# PocketCHIP-v1_0.net
KiCad netlist of a schematic drawn in EAGLE
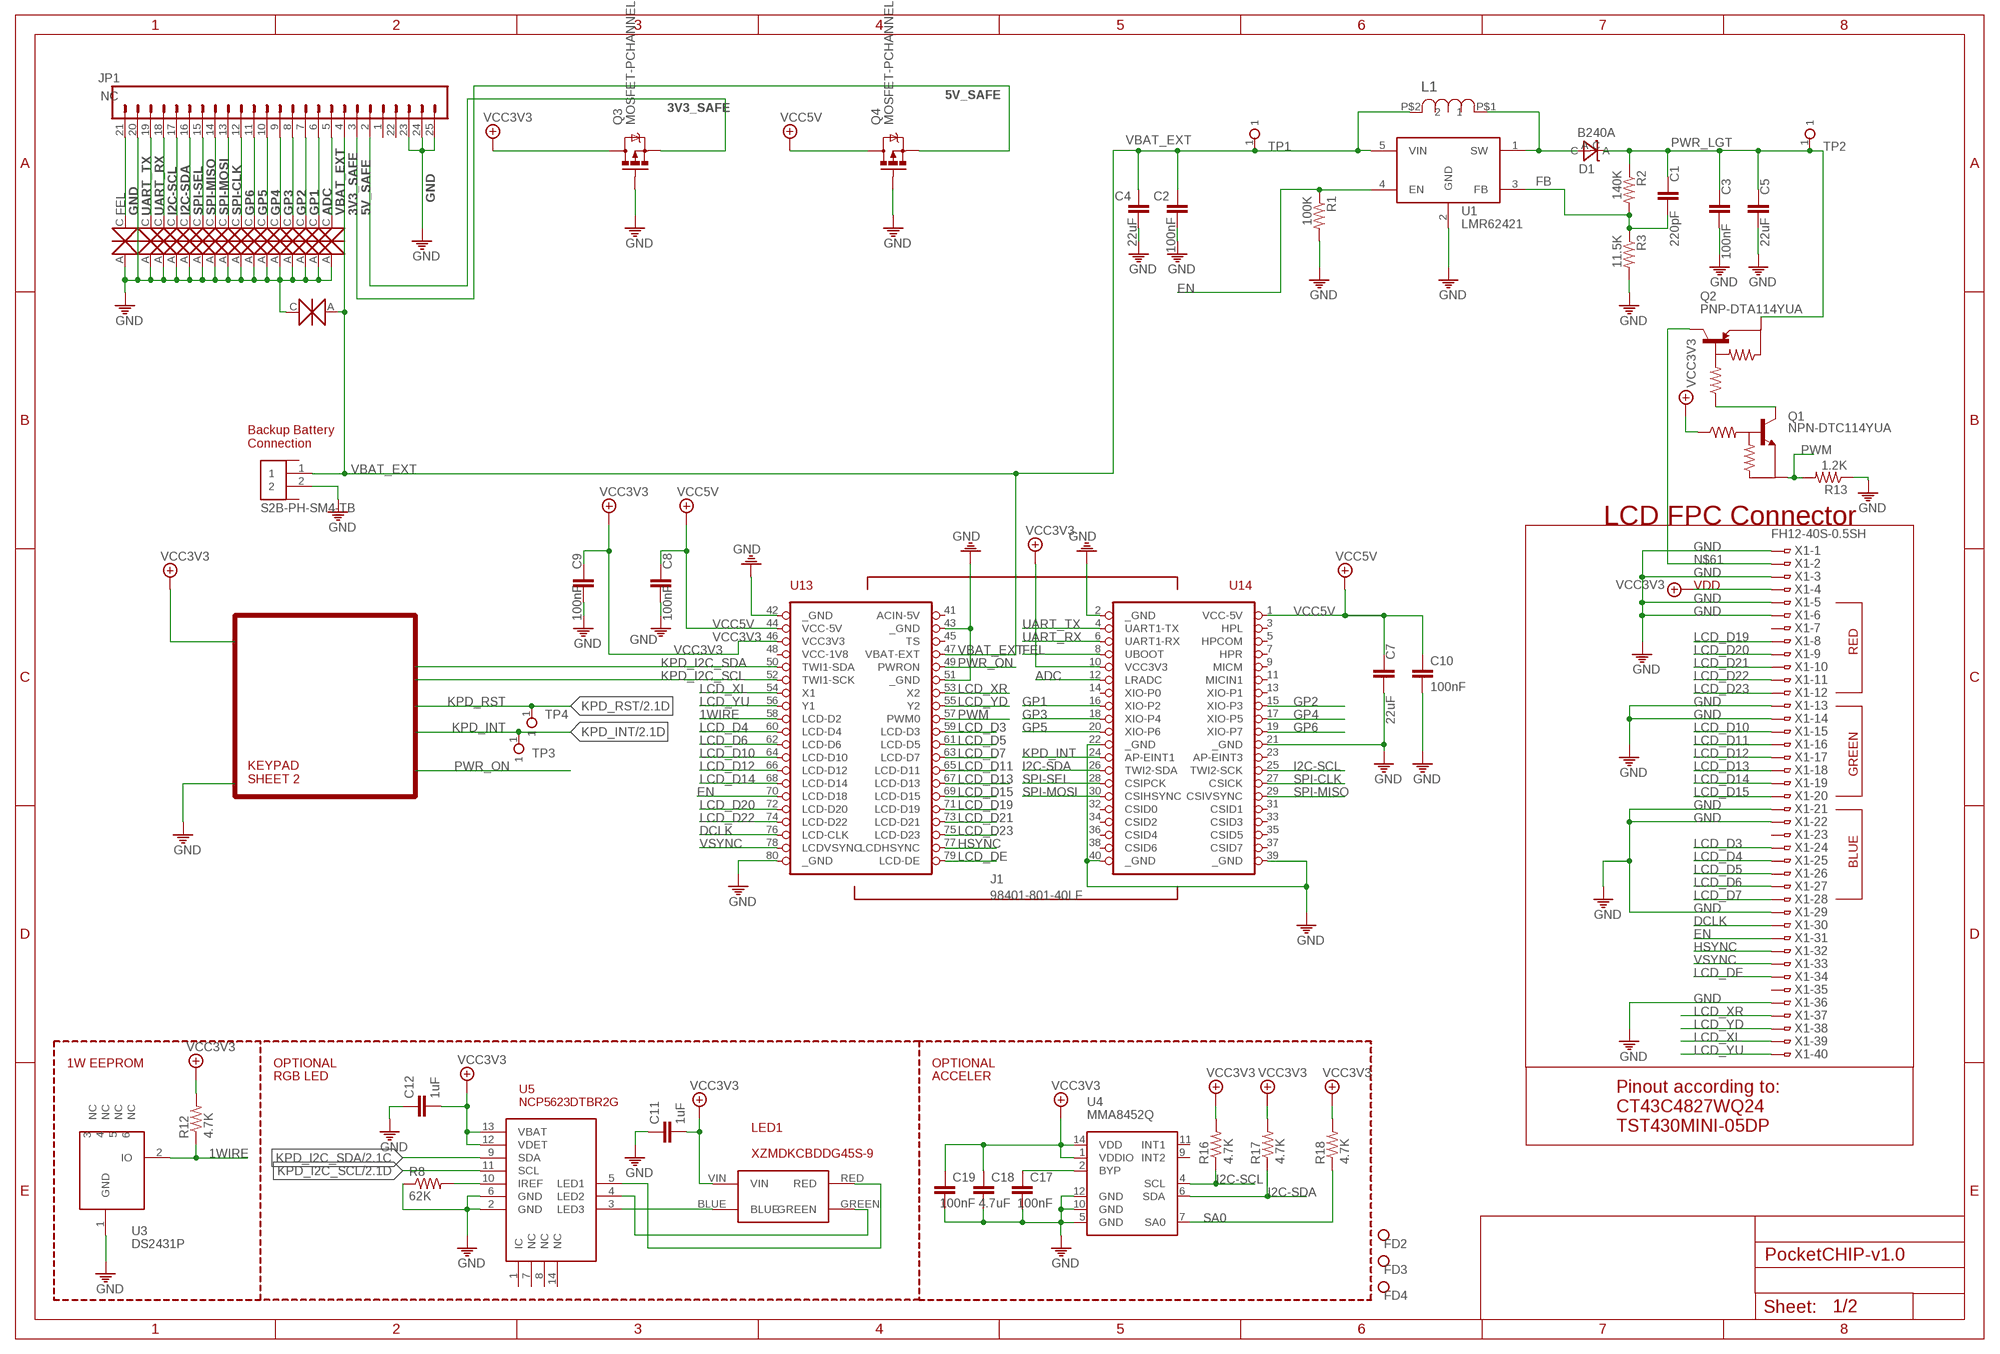
[diagram p0: schematic, sheet 1]
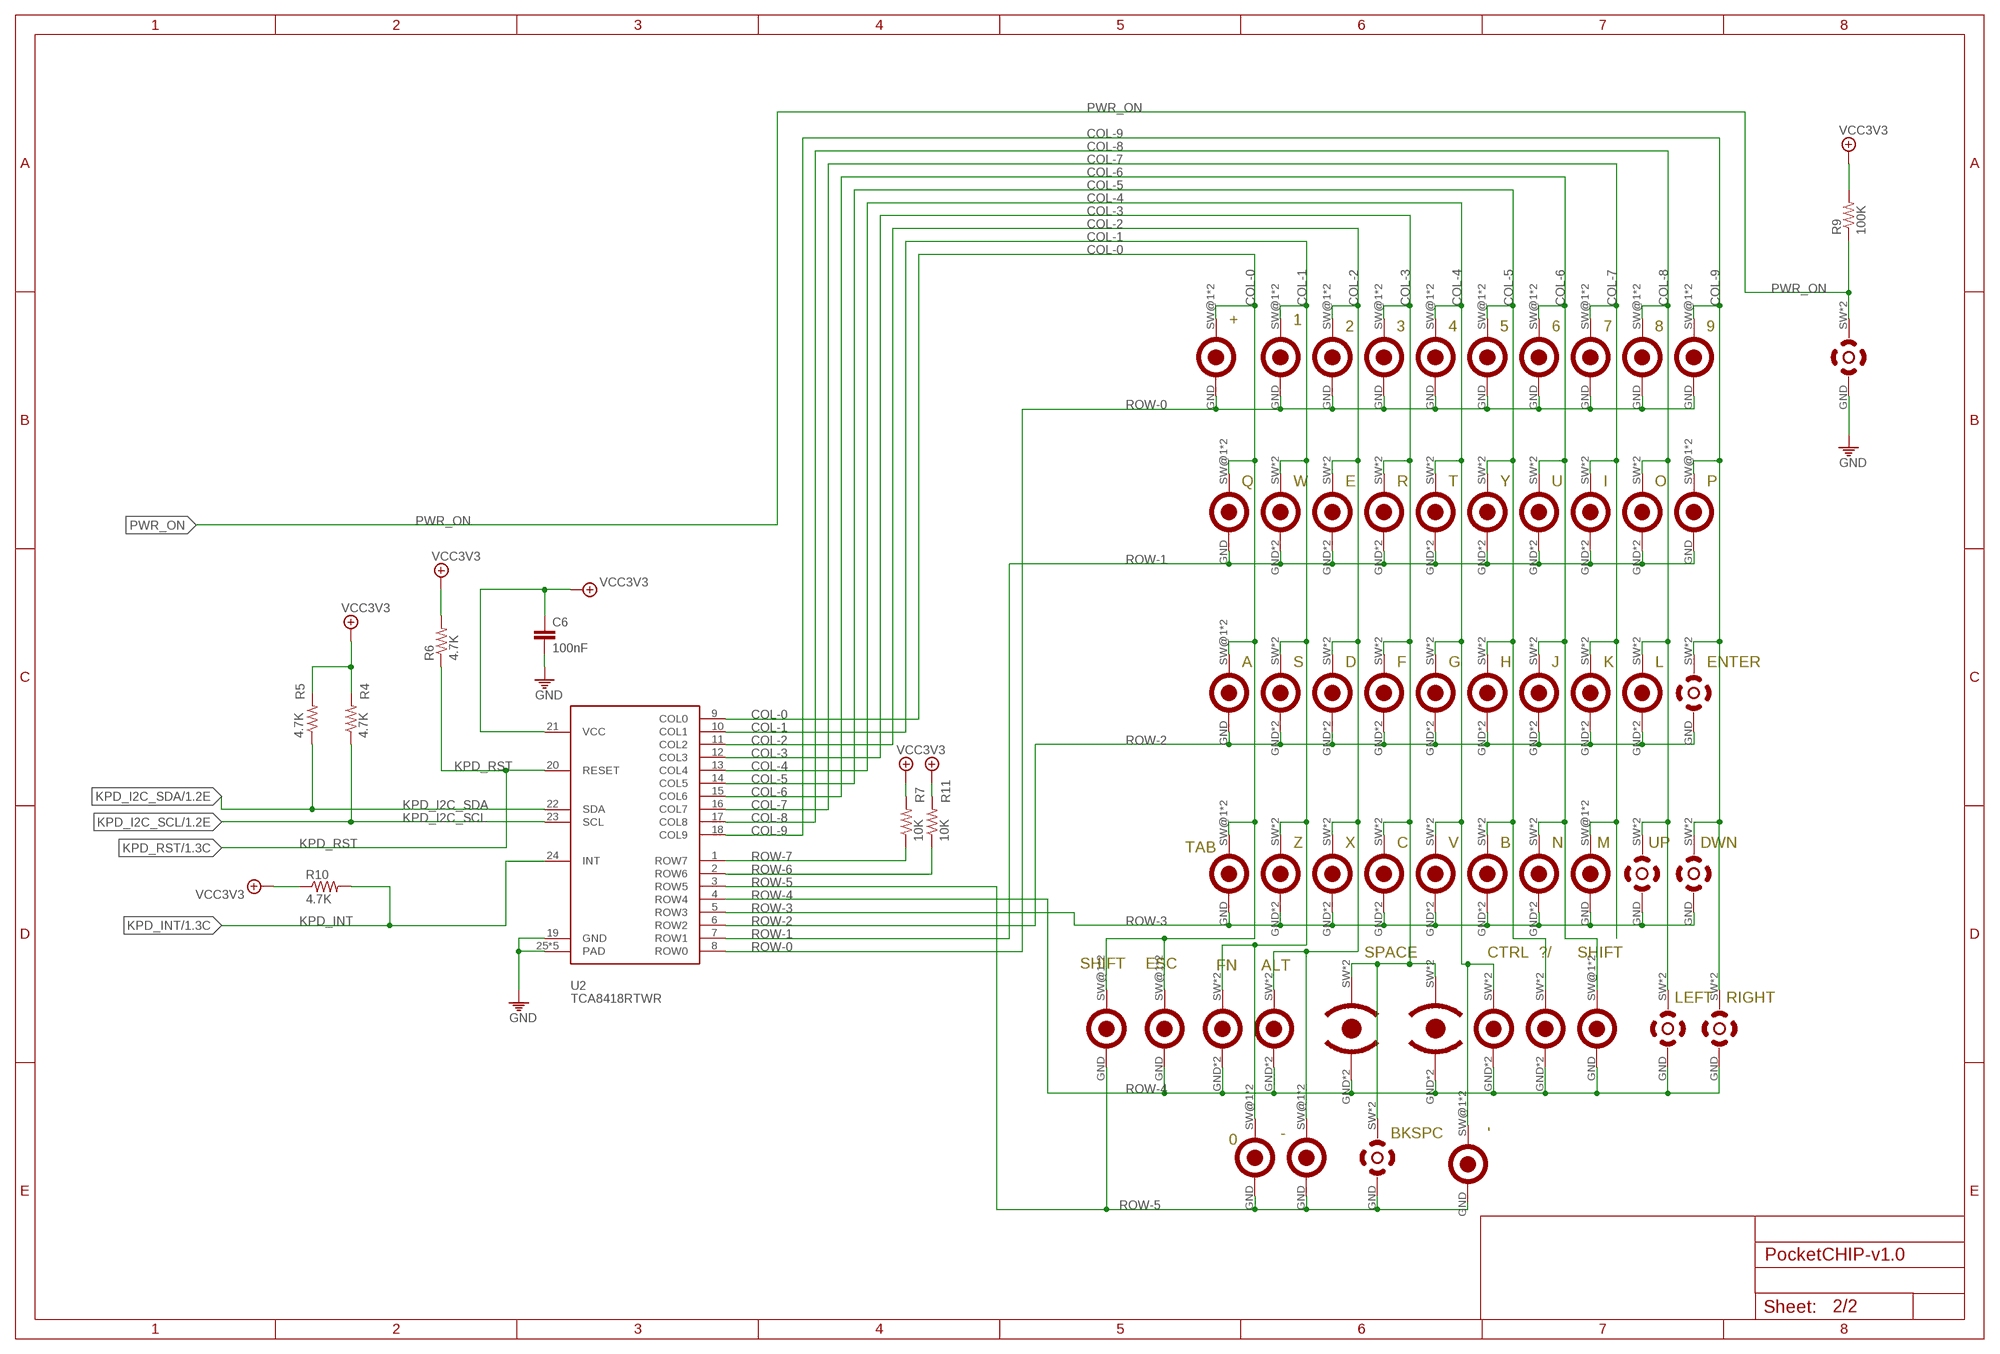
[diagram p1: schematic, sheet 2]

(export (version "E")
  (design (tool "Eeschema 10.0.6"))
  (components
    (comp (ref "C1")
      (value "220pF")
      (footprint "eagle-import:C0402")
      (fields (field (name "MFG") "DIGIIKEY") (field (name "VENDOR_PART_NUMBER") "C0402C221J5GACTU"))
      (libsource (lib "eagle-import") (part "C0402_220PF_50V_5%"))
    )
    (comp (ref "C2")
      (value "100nF")
      (footprint "eagle-import:C0402")
      (fields (field (name "MFG") "DIGIIKEY") (field (name "VENDOR_PART_NUMBER") "C1005X5R1E104K050BC"))
      (libsource (lib "eagle-import") (part "C0402_100NF_50V_10%"))
    )
    (comp (ref "C3")
      (value "100nF")
      (footprint "eagle-import:C0402")
      (fields (field (name "MFG") "DIGIIKEY") (field (name "VENDOR_PART_NUMBER") "C1005X5R1E104K050BC"))
      (libsource (lib "eagle-import") (part "C0402_100NF_50V_10%"))
    )
    (comp (ref "C4")
      (value "22uF")
      (footprint "eagle-import:C1206")
      (fields (field (name "MFG") "DIGIKEY") (field (name "VENDOR_PART_NUMBER") "C3216X5R1V226M160AC"))
      (libsource (lib "eagle-import") (part "C1206_22UF_50V_10%"))
    )
    (comp (ref "C5")
      (value "22uF")
      (footprint "eagle-import:C1206")
      (fields (field (name "MFG") "DIGIKEY") (field (name "VENDOR_PART_NUMBER") "C3216X5R1V226M160AC"))
      (libsource (lib "eagle-import") (part "C1206_22UF_50V_10%"))
    )
    (comp (ref "C7")
      (value "22uF")
      (footprint "eagle-import:C1206")
      (fields (field (name "MFG") "DIGIKEY") (field (name "VENDOR_PART_NUMBER") "C3216X5R1V226M160AC"))
      (libsource (lib "eagle-import") (part "C1206_22UF_50V_10%"))
    )
    (comp (ref "C8")
      (value "100nF")
      (footprint "eagle-import:C0402")
      (fields (field (name "MFG") "DIGIIKEY") (field (name "VENDOR_PART_NUMBER") "C1005X5R1E104K050BC"))
      (libsource (lib "eagle-import") (part "C0402_100NF_50V_10%"))
    )
    (comp (ref "C9")
      (value "100nF")
      (footprint "eagle-import:C0402")
      (fields (field (name "MFG") "DIGIIKEY") (field (name "VENDOR_PART_NUMBER") "C1005X5R1E104K050BC"))
      (libsource (lib "eagle-import") (part "C0402_100NF_50V_10%"))
    )
    (comp (ref "C10")
      (value "100nF")
      (footprint "eagle-import:C0402")
      (fields (field (name "MFG") "DIGIIKEY") (field (name "VENDOR_PART_NUMBER") "C1005X5R1E104K050BC"))
      (libsource (lib "eagle-import") (part "C0402_100NF_50V_10%"))
    )
    (comp (ref "C11")
      (value "1uF")
      (footprint "eagle-import:C0402")
      (fields (field (name "MFG") "DIGIIKEY") (field (name "VENDOR_PART_NUMBER") "C1005X5R1E104K050BC"))
      (libsource (lib "eagle-import") (part "C0402_1UF_50V_10%"))
    )
    (comp (ref "C12")
      (value "1uF")
      (footprint "eagle-import:C0402")
      (fields (field (name "MFG") "DIGIIKEY") (field (name "VENDOR_PART_NUMBER") "C1005X5R1E104K050BC"))
      (libsource (lib "eagle-import") (part "C0402_1UF_50V_10%"))
    )
    (comp (ref "C17")
      (value "100nF")
      (footprint "eagle-import:C0402")
      (fields (field (name "MFG") "DIGIIKEY") (field (name "VENDOR_PART_NUMBER") "C1005X5R1E104K050BC"))
      (libsource (lib "eagle-import") (part "PocketCHIP-Components-v0.71_C0402_100NF_50V_10%"))
    )
    (comp (ref "C18")
      (value "4.7uF")
      (footprint "eagle-import:C0402")
      (fields (field (name "MFG") "DIGIIKEY") (field (name "VENDOR_PART_NUMBER") "C1005X5R1E104K050BC"))
      (libsource (lib "eagle-import") (part "PocketCHIP-Components-v0.71_C0402_100NF_50V_10%"))
    )
    (comp (ref "C19")
      (value "100nF")
      (footprint "eagle-import:C0402")
      (fields (field (name "MFG") "DIGIIKEY") (field (name "VENDOR_PART_NUMBER") "C1005X5R1E104K050BC"))
      (libsource (lib "eagle-import") (part "PocketCHIP-Components-v0.71_C0402_100NF_50V_10%"))
    )
    (comp (ref "D1")
      (value "B240A")
      (footprint "eagle-import:DO-214AC")
      (fields (field (name "MFG") "DIGIKEY") (field (name "VENDOR_PART_NUMBER") "B240A-13-F"))
      (libsource (lib "eagle-import") (part "DIODE_SCHTKY_B240"))
    )
    (comp (ref "ESD1")
      (value "ESD5Z2.5T1G")
      (footprint "eagle-import:SOD523")
      (libsource (lib "eagle-import") (part "ESD5Z2.5T1G"))
    )
    (comp (ref "ESD2")
      (value "ESD5Z2.5T1G")
      (footprint "eagle-import:SOD523")
      (libsource (lib "eagle-import") (part "ESD5Z2.5T1G"))
    )
    (comp (ref "ESD3")
      (value "ESD5Z2.5T1G")
      (footprint "eagle-import:SOD523")
      (libsource (lib "eagle-import") (part "ESD5Z2.5T1G"))
    )
    (comp (ref "ESD4")
      (value "ESD5Z2.5T1G")
      (footprint "eagle-import:SOD523")
      (libsource (lib "eagle-import") (part "ESD5Z2.5T1G"))
    )
    (comp (ref "ESD5")
      (value "ESD5Z2.5T1G")
      (footprint "eagle-import:SOD523")
      (libsource (lib "eagle-import") (part "ESD5Z2.5T1G"))
    )
    (comp (ref "ESD6")
      (value "ESD5Z2.5T1G")
      (footprint "eagle-import:SOD523")
      (libsource (lib "eagle-import") (part "ESD5Z2.5T1G"))
    )
    (comp (ref "ESD7")
      (value "ESD5Z2.5T1G")
      (footprint "eagle-import:SOD523")
      (libsource (lib "eagle-import") (part "ESD5Z2.5T1G"))
    )
    (comp (ref "ESD8")
      (value "ESD5Z2.5T1G")
      (footprint "eagle-import:SOD523")
      (libsource (lib "eagle-import") (part "ESD5Z2.5T1G"))
    )
    (comp (ref "ESD9")
      (value "ESD5Z2.5T1G")
      (footprint "eagle-import:SOD523")
      (libsource (lib "eagle-import") (part "ESD5Z2.5T1G"))
    )
    (comp (ref "ESD10")
      (value "ESD5Z2.5T1G")
      (footprint "eagle-import:SOD523")
      (libsource (lib "eagle-import") (part "ESD5Z2.5T1G"))
    )
    (comp (ref "ESD11")
      (value "ESD5Z2.5T1G")
      (footprint "eagle-import:SOD523")
      (libsource (lib "eagle-import") (part "ESD5Z2.5T1G"))
    )
    (comp (ref "ESD12")
      (value "ESD5Z2.5T1G")
      (footprint "eagle-import:SOD523")
      (libsource (lib "eagle-import") (part "ESD5Z2.5T1G"))
    )
    (comp (ref "ESD13")
      (value "ESD5Z2.5T1G")
      (footprint "eagle-import:SOD523")
      (libsource (lib "eagle-import") (part "ESD5Z2.5T1G"))
    )
    (comp (ref "ESD14")
      (value "ESD5Z2.5T1G")
      (footprint "eagle-import:SOD523")
      (libsource (lib "eagle-import") (part "ESD5Z2.5T1G"))
    )
    (comp (ref "ESD15")
      (value "ESD5Z2.5T1G")
      (footprint "eagle-import:SOD523")
      (libsource (lib "eagle-import") (part "ESD5Z2.5T1G"))
    )
    (comp (ref "ESD16")
      (value "ESD5Z2.5T1G")
      (footprint "eagle-import:SOD523")
      (libsource (lib "eagle-import") (part "ESD5Z2.5T1G"))
    )
    (comp (ref "ESD17")
      (value "ESD5Z2.5T1G")
      (footprint "eagle-import:SOD523")
      (libsource (lib "eagle-import") (part "ESD5Z2.5T1G"))
    )
    (comp (ref "FD2")
      (value "FIDUCIAL")
      (footprint "eagle-import:FIDUCIAL_1MM")
      (fields (field (name "PART_NUMBER") "RB00000042"))
      (libsource (lib "eagle-import") (part "FIDUCIAL"))
    )
    (comp (ref "FD3")
      (value "FIDUCIAL")
      (footprint "eagle-import:FIDUCIAL_1MM")
      (fields (field (name "PART_NUMBER") "RB00000042"))
      (libsource (lib "eagle-import") (part "FIDUCIAL"))
    )
    (comp (ref "FD4")
      (value "FIDUCIAL")
      (footprint "eagle-import:FIDUCIAL_1MM")
      (fields (field (name "PART_NUMBER") "RB00000042"))
      (libsource (lib "eagle-import") (part "FIDUCIAL"))
    )
    (comp (ref "J1")
      (value "98401-801-40LF")
      (footprint "eagle-import:98401-801-40LF")
      (libsource (lib "eagle-import") (part "98401-801-40LF"))
    )
    (comp (ref "J3")
      (value "S2B-PH-SM4-TB")
      (footprint "eagle-import:S2B-PH-SM4-TB")
      (fields (field (name "MFG") "DIGIKEY") (field (name "VENDOR_PART_NUMBER") "S2B-PH-SM4-TB(LF)(SN)"))
      (libsource (lib "eagle-import") (part "S2B-PH-SM4-TB"))
    )
    (comp (ref "JP1")
      (value "NC")
      (footprint "eagle-import:1X20_LOCK_LONGPADS")
      (libsource (lib "eagle-import") (part "M20LOCK_LONGPADS"))
    )
    (comp (ref "L1")
      (value "SRN6045-100M")
      (footprint "eagle-import:SRN6045")
      (fields (field (name "MFG") "DIGIKEY"))
      (libsource (lib "eagle-import") (part "SRN6045-100M"))
    )
    (comp (ref "LED1")
      (value "XZMDKCBDDG45S-9")
      (footprint "eagle-import:XZMDKCBDDG45S-9")
      (libsource (lib "eagle-import") (part "XZMDKCBDDG45S-9"))
    )
    (comp (ref "Q1")
      (value "NPN-DTC114YUA")
      (footprint "eagle-import:SOT323")
      (libsource (lib "eagle-import") (part "NPN-DTC114YUA"))
    )
    (comp (ref "Q2")
      (value "PNP-DTA114YUA")
      (footprint "eagle-import:SOT323")
      (libsource (lib "eagle-import") (part "PNP-DTA114YUA"))
    )
    (comp (ref "Q3")
      (value "MOSFET-PCHANNEL")
      (footprint "eagle-import:SOT23-3")
      (libsource (lib "eagle-import") (part "MOSFET-PCHANNEL"))
    )
    (comp (ref "Q4")
      (value "MOSFET-PCHANNEL")
      (footprint "eagle-import:SOT23-3")
      (libsource (lib "eagle-import") (part "MOSFET-PCHANNEL"))
    )
    (comp (ref "R1")
      (value "100K")
      (footprint "eagle-import:R0402")
      (fields (field (name "MFG") "DIGIKEY") (field (name "VENDOR_PART_NUMBER") "ERJ-2GEJ104X"))
      (libsource (lib "eagle-import") (part "R0402_100K_5%"))
    )
    (comp (ref "R2")
      (value "140K")
      (footprint "eagle-import:R0402")
      (fields (field (name "MFG") "DIGIKEY") (field (name "VENDOR_PART_NUMBER") "RC0402FR-07140KL"))
      (libsource (lib "eagle-import") (part "R0402_140K_1%"))
    )
    (comp (ref "R3")
      (value "11.5K")
      (footprint "eagle-import:R0402")
      (fields (field (name "MFG") "DIGIKEY") (field (name "VENDOR_PART_NUMBER") "RC0402FR-0711K5L"))
      (libsource (lib "eagle-import") (part "R0402_11K5_1%"))
    )
    (comp (ref "R8")
      (value "62K")
      (footprint "eagle-import:R0402")
      (fields (field (name "MFG") "DIGIKEY") (field (name "VENDOR_PART_NUMBER") "ERJ-2GEJ102X"))
      (libsource (lib "eagle-import") (part "R0402_62K_5%"))
    )
    (comp (ref "R12")
      (value "4.7K")
      (footprint "eagle-import:R0402")
      (fields (field (name "MFG") "DIGIKEY") (field (name "VENDOR_PART_NUMBER") "ERJ-2GEJ472X"))
      (libsource (lib "eagle-import") (part "R0402_4K7_5%"))
    )
    (comp (ref "R13")
      (value "1.2K")
      (footprint "eagle-import:R0402")
      (fields (field (name "MFG") "DIGIKEY") (field (name "VENDOR_PART_NUMBER") "ERJ-2GEJ102X"))
      (libsource (lib "eagle-import") (part "PocketCHIP-Components-v0.72_R0402_1K_5%"))
    )
    (comp (ref "R16")
      (value "4.7K")
      (footprint "eagle-import:R0402")
      (fields (field (name "MFG") "DIGIKEY") (field (name "VENDOR_PART_NUMBER") "ERJ-2GEJ472X"))
      (libsource (lib "eagle-import") (part "PocketCHIP-Components-v0.71_R0402_4K7_5%"))
    )
    (comp (ref "R17")
      (value "4.7K")
      (footprint "eagle-import:R0402")
      (fields (field (name "MFG") "DIGIKEY") (field (name "VENDOR_PART_NUMBER") "ERJ-2GEJ472X"))
      (libsource (lib "eagle-import") (part "PocketCHIP-Components-v0.71_R0402_4K7_5%"))
    )
    (comp (ref "R18")
      (value "4.7K")
      (footprint "eagle-import:R0402")
      (fields (field (name "MFG") "DIGIKEY") (field (name "VENDOR_PART_NUMBER") "ERJ-2GEJ472X"))
      (libsource (lib "eagle-import") (part "PocketCHIP-Components-v0.71_R0402_4K7_5%"))
    )
    (comp (ref "TP1")
      (value "N.C")
      (footprint "eagle-import:TP_19_5")
      (fields (field (name "PART_NUMBER") "RB00000140"))
      (libsource (lib "eagle-import") (part "PocketCHIP-Components-v0.71_TP_SMD_0_5MM"))
    )
    (comp (ref "TP2")
      (value "N.C")
      (footprint "eagle-import:TP_19_5")
      (fields (field (name "PART_NUMBER") "RB00000140"))
      (libsource (lib "eagle-import") (part "PocketCHIP-Components-v0.71_TP_SMD_0_5MM"))
    )
    (comp (ref "TP3")
      (value "N.C")
      (footprint "eagle-import:TP_19_5")
      (fields (field (name "PART_NUMBER") "RB00000140"))
      (libsource (lib "eagle-import") (part "TP_SMD_0_5MM"))
    )
    (comp (ref "TP4")
      (value "N.C")
      (footprint "eagle-import:TP_19_5")
      (fields (field (name "PART_NUMBER") "RB00000140"))
      (libsource (lib "eagle-import") (part "TP_SMD_0_5MM"))
    )
    (comp (ref "U1")
      (value "LMR62421")
      (footprint "eagle-import:SOT23-5")
      (fields (field (name "MFG") "DIGIKEY") (field (name "VENDOR_PART_NUMBER") "LMR62421XMFE/NOPB"))
      (libsource (lib "eagle-import") (part "LMR62421"))
    )
    (comp (ref "U3")
      (value "DS2431P")
      (footprint "eagle-import:TSOC6")
      (fields (field (name "MFG") "DIGIKEY") (field (name "VENDOR_PART_NUMBER") "DS2431P+T&R"))
      (libsource (lib "eagle-import") (part "DS2431P"))
    )
    (comp (ref "U4")
      (value "MMA8452Q")
      (footprint "eagle-import:QFN-16_0.5MM")
      (libsource (lib "eagle-import") (part "MMA8452Q"))
    )
    (comp (ref "U5")
      (value "NCP5623DTBR2G")
      (footprint "eagle-import:TSSOP14")
      (libsource (lib "eagle-import") (part "NCP5623DTBR2G"))
    )
    (comp (ref "X1")
      (value "FH12-40S-0.5SH")
      (footprint "eagle-import:FH12-40S-0.5SH")
      (fields (field (name "MFG") "DIGIKEY") (field (name "VENDOR_PART_NUMBER") "FH12-40S-0.5SH(55)"))
      (libsource (lib "eagle-import") (part "FH12-40S-0.5SH"))
    )
    (comp (ref "'")
      (value "M272201PAD")
      (footprint "eagle-import:SNAPDOME_M27220_1PAD")
      (libsource (lib "eagle-import") (part "M272201PAD"))
    )
    (comp (ref "+")
      (value "M272201PAD")
      (footprint "eagle-import:SNAPDOME_M27220_1PAD")
      (libsource (lib "eagle-import") (part "M272201PAD"))
    )
    (comp (ref "-")
      (value "M272201PAD")
      (footprint "eagle-import:SNAPDOME_M27220_1PAD")
      (libsource (lib "eagle-import") (part "M272201PAD"))
    )
    (comp (ref "0")
      (value "M272201PAD")
      (footprint "eagle-import:SNAPDOME_M27220_1PAD")
      (libsource (lib "eagle-import") (part "M272201PAD"))
    )
    (comp (ref "1")
      (value "M272201PAD")
      (footprint "eagle-import:SNAPDOME_M27220_1PAD")
      (libsource (lib "eagle-import") (part "M272201PAD"))
    )
    (comp (ref "2")
      (value "M272201PAD")
      (footprint "eagle-import:SNAPDOME_M27220_1PAD")
      (libsource (lib "eagle-import") (part "M272201PAD"))
    )
    (comp (ref "3")
      (value "M272201PAD")
      (footprint "eagle-import:SNAPDOME_M27220_1PAD")
      (libsource (lib "eagle-import") (part "M272201PAD"))
    )
    (comp (ref "4")
      (value "M272201PAD")
      (footprint "eagle-import:SNAPDOME_M27220_1PAD")
      (libsource (lib "eagle-import") (part "M272201PAD"))
    )
    (comp (ref "5")
      (value "M272201PAD")
      (footprint "eagle-import:SNAPDOME_M27220_1PAD")
      (libsource (lib "eagle-import") (part "M272201PAD"))
    )
    (comp (ref "6")
      (value "M272201PAD")
      (footprint "eagle-import:SNAPDOME_M27220_1PAD")
      (libsource (lib "eagle-import") (part "M272201PAD"))
    )
    (comp (ref "7")
      (value "M272201PAD")
      (footprint "eagle-import:SNAPDOME_M27220_1PAD")
      (libsource (lib "eagle-import") (part "M272201PAD"))
    )
    (comp (ref "8")
      (value "M272201PAD")
      (footprint "eagle-import:SNAPDOME_M27220_1PAD")
      (libsource (lib "eagle-import") (part "M272201PAD"))
    )
    (comp (ref "9")
      (value "M272201PAD")
      (footprint "eagle-import:SNAPDOME_M27220_1PAD")
      (libsource (lib "eagle-import") (part "M272201PAD"))
    )
    (comp (ref "?/")
      (value "M27220")
      (footprint "eagle-import:SNAPDOME_M27220")
      (libsource (lib "eagle-import") (part "M27220"))
    )
    (comp (ref "A")
      (value "M272201PAD")
      (footprint "eagle-import:SNAPDOME_M27220_1PAD")
      (libsource (lib "eagle-import") (part "M272201PAD"))
    )
    (comp (ref "ALT")
      (value "M27220")
      (footprint "eagle-import:SNAPDOME_M27220")
      (libsource (lib "eagle-import") (part "M27220"))
    )
    (comp (ref "B")
      (value "M27220")
      (footprint "eagle-import:SNAPDOME_M27220")
      (libsource (lib "eagle-import") (part "M27220"))
    )
    (comp (ref "BKSPC")
      (value "BL08260")
      (footprint "eagle-import:SNAPDOME_BL08260")
      (libsource (lib "eagle-import") (part "BL08260"))
    )
    (comp (ref "C")
      (value "M27220")
      (footprint "eagle-import:SNAPDOME_M27220")
      (libsource (lib "eagle-import") (part "M27220"))
    )
    (comp (ref "C6")
      (value "100nF")
      (footprint "eagle-import:C0402")
      (fields (field (name "MFG") "DIGIIKEY") (field (name "VENDOR_PART_NUMBER") "C1005X5R1E104K050BC"))
      (libsource (lib "eagle-import") (part "C0402_100NF_50V_10%"))
    )
    (comp (ref "CTRL")
      (value "M272201PAD")
      (footprint "eagle-import:SNAPDOME_M27220_1PAD")
      (libsource (lib "eagle-import") (part "M272201PAD"))
    )
    (comp (ref "D")
      (value "M27220")
      (footprint "eagle-import:SNAPDOME_M27220")
      (libsource (lib "eagle-import") (part "M27220"))
    )
    (comp (ref "DWN")
      (value "E9-TDF-340")
      (footprint "eagle-import:SNAPDOME_E9-TDF-340")
      (libsource (lib "eagle-import") (part "E9-TDF-340"))
    )
    (comp (ref "E")
      (value "M27220")
      (footprint "eagle-import:SNAPDOME_M27220")
      (libsource (lib "eagle-import") (part "M27220"))
    )
    (comp (ref "ENTER")
      (value "BL08260")
      (footprint "eagle-import:SNAPDOME_BL08260")
      (libsource (lib "eagle-import") (part "BL08260"))
    )
    (comp (ref "ESC")
      (value "M272201PAD")
      (footprint "eagle-import:SNAPDOME_M27220_1PAD")
      (libsource (lib "eagle-import") (part "M272201PAD"))
    )
    (comp (ref "F")
      (value "M27220")
      (footprint "eagle-import:SNAPDOME_M27220")
      (libsource (lib "eagle-import") (part "M27220"))
    )
    (comp (ref "FN")
      (value "M27220")
      (footprint "eagle-import:SNAPDOME_M27220")
      (libsource (lib "eagle-import") (part "M27220"))
    )
    (comp (ref "G")
      (value "M27220")
      (footprint "eagle-import:SNAPDOME_M27220")
      (libsource (lib "eagle-import") (part "M27220"))
    )
    (comp (ref "H")
      (value "M27220")
      (footprint "eagle-import:SNAPDOME_M27220")
      (libsource (lib "eagle-import") (part "M27220"))
    )
    (comp (ref "I")
      (value "M27220")
      (footprint "eagle-import:SNAPDOME_M27220")
      (libsource (lib "eagle-import") (part "M27220"))
    )
    (comp (ref "J")
      (value "M27220")
      (footprint "eagle-import:SNAPDOME_M27220")
      (libsource (lib "eagle-import") (part "M27220"))
    )
    (comp (ref "K")
      (value "M27220")
      (footprint "eagle-import:SNAPDOME_M27220")
      (libsource (lib "eagle-import") (part "M27220"))
    )
    (comp (ref "L")
      (value "M27220")
      (footprint "eagle-import:SNAPDOME_M27220")
      (libsource (lib "eagle-import") (part "M27220"))
    )
    (comp (ref "LEFT")
      (value "E9-TDF-340")
      (footprint "eagle-import:SNAPDOME_E9-TDF-340")
      (libsource (lib "eagle-import") (part "E9-TDF-340"))
    )
    (comp (ref "M")
      (value "M272201PAD")
      (footprint "eagle-import:SNAPDOME_M27220_1PAD")
      (libsource (lib "eagle-import") (part "M272201PAD"))
    )
    (comp (ref "N")
      (value "M27220")
      (footprint "eagle-import:SNAPDOME_M27220")
      (libsource (lib "eagle-import") (part "M27220"))
    )
    (comp (ref "O")
      (value "M27220")
      (footprint "eagle-import:SNAPDOME_M27220")
      (libsource (lib "eagle-import") (part "M27220"))
    )
    (comp (ref "P")
      (value "M272201PAD")
      (footprint "eagle-import:SNAPDOME_M27220_1PAD")
      (libsource (lib "eagle-import") (part "M272201PAD"))
    )
    (comp (ref "PWR")
      (value "100105")
      (footprint "eagle-import:SNAPDOME_100105")
      (libsource (lib "eagle-import") (part "100105"))
    )
    (comp (ref "Q")
      (value "M272201PAD")
      (footprint "eagle-import:SNAPDOME_M27220_1PAD")
      (libsource (lib "eagle-import") (part "M272201PAD"))
    )
    (comp (ref "R")
      (value "M27220")
      (footprint "eagle-import:SNAPDOME_M27220")
      (libsource (lib "eagle-import") (part "M27220"))
    )
    (comp (ref "R4")
      (value "4.7K")
      (footprint "eagle-import:R0402")
      (fields (field (name "MFG") "DIGIKEY") (field (name "VENDOR_PART_NUMBER") "ERJ-2GEJ472X"))
      (libsource (lib "eagle-import") (part "R0402_4K7_5%"))
    )
    (comp (ref "R5")
      (value "4.7K")
      (footprint "eagle-import:R0402")
      (fields (field (name "MFG") "DIGIKEY") (field (name "VENDOR_PART_NUMBER") "ERJ-2GEJ472X"))
      (libsource (lib "eagle-import") (part "R0402_4K7_5%"))
    )
    (comp (ref "R6")
      (value "4.7K")
      (footprint "eagle-import:R0402")
      (fields (field (name "MFG") "DIGIKEY") (field (name "VENDOR_PART_NUMBER") "ERJ-2GEJ102X"))
      (libsource (lib "eagle-import") (part "R0402_1K_5%"))
    )
    (comp (ref "R7")
      (value "10K")
      (footprint "eagle-import:R0402")
      (fields (field (name "MFG") "DIGIKEY") (field (name "VENDOR_PART_NUMBER") "ERJ-2GEJ472X"))
      (libsource (lib "eagle-import") (part "R0402_4K7_5%"))
    )
    (comp (ref "R9")
      (value "100K")
      (footprint "eagle-import:R0402")
      (fields (field (name "MFG") "DIGIKEY") (field (name "VENDOR_PART_NUMBER") "ERJ-2GEJ104X"))
      (libsource (lib "eagle-import") (part "R0402_100K_5%"))
    )
    (comp (ref "R10")
      (value "4.7K")
      (footprint "eagle-import:R0402")
      (fields (field (name "MFG") "DIGIKEY") (field (name "VENDOR_PART_NUMBER") "ERJ-2GEJ102X"))
      (libsource (lib "eagle-import") (part "R0402_1K_5%"))
    )
    (comp (ref "R11")
      (value "10K")
      (footprint "eagle-import:R0402")
      (fields (field (name "MFG") "DIGIKEY") (field (name "VENDOR_PART_NUMBER") "ERJ-2GEJ472X"))
      (libsource (lib "eagle-import") (part "R0402_4K7_5%"))
    )
    (comp (ref "RIGHT")
      (value "E9-TDF-340")
      (footprint "eagle-import:SNAPDOME_E9-TDF-340")
      (libsource (lib "eagle-import") (part "E9-TDF-340"))
    )
    (comp (ref "S")
      (value "M27220")
      (footprint "eagle-import:SNAPDOME_M27220")
      (libsource (lib "eagle-import") (part "M27220"))
    )
    (comp (ref "SHFT")
      (value "M272201PAD")
      (footprint "eagle-import:SNAPDOME_M27220_1PAD")
      (libsource (lib "eagle-import") (part "M272201PAD"))
    )
    (comp (ref "SHIFT")
      (value "M272201PAD")
      (footprint "eagle-import:SNAPDOME_M27220_1PAD")
      (libsource (lib "eagle-import") (part "M272201PAD"))
    )
    (comp (ref "SPACEL")
      (value "E.22-ONN-230")
      (footprint "eagle-import:SNAPDOME_E.22-ONN-230")
      (libsource (lib "eagle-import") (part "E.22-ONN-230"))
    )
    (comp (ref "SPACER")
      (value "E.22-ONN-230")
      (footprint "eagle-import:SNAPDOME_E.22-ONN-230")
      (libsource (lib "eagle-import") (part "E.22-ONN-230"))
    )
    (comp (ref "T")
      (value "M27220")
      (footprint "eagle-import:SNAPDOME_M27220")
      (libsource (lib "eagle-import") (part "M27220"))
    )
    (comp (ref "TAB")
      (value "M27220")
      (footprint "eagle-import:SNAPDOME_M27220")
      (libsource (lib "eagle-import") (part "M27220"))
    )
    (comp (ref "U")
      (value "M27220")
      (footprint "eagle-import:SNAPDOME_M27220")
      (libsource (lib "eagle-import") (part "M27220"))
    )
    (comp (ref "U2")
      (value "TCA8418RTWR")
      (footprint "eagle-import:WQFN24")
      (fields (field (name "MFG") "DIGIKEY"))
      (libsource (lib "eagle-import") (part "TCA8418RTWR"))
    )
    (comp (ref "UP")
      (value "E9-TDF-340")
      (footprint "eagle-import:SNAPDOME_E9-TDF-340")
      (libsource (lib "eagle-import") (part "E9-TDF-340"))
    )
    (comp (ref "V")
      (value "M27220")
      (footprint "eagle-import:SNAPDOME_M27220")
      (libsource (lib "eagle-import") (part "M27220"))
    )
    (comp (ref "W")
      (value "M27220")
      (footprint "eagle-import:SNAPDOME_M27220")
      (libsource (lib "eagle-import") (part "M27220"))
    )
    (comp (ref "X")
      (value "M27220")
      (footprint "eagle-import:SNAPDOME_M27220")
      (libsource (lib "eagle-import") (part "M27220"))
    )
    (comp (ref "Y")
      (value "M27220")
      (footprint "eagle-import:SNAPDOME_M27220")
      (libsource (lib "eagle-import") (part "M27220"))
    )
    (comp (ref "Z")
      (value "M27220")
      (footprint "eagle-import:SNAPDOME_M27220")
      (libsource (lib "eagle-import") (part "M27220"))
    )
  )
  (nets
    (net (code "1") (name "1WIRE") (class "Default")
      (node (ref "J1") (pin "58") (pinfunction "LCD-D2_58") (pintype "passive"))
      (node (ref "R12") (pin "1") (pinfunction "1_1") (pintype "passive"))
      (node (ref "U3") (pin "2") (pinfunction "IO_2") (pintype "bidirectional"))
    )
    (net (code "2") (name "3V3_SAFE") (class "Default")
      (node (ref "JP1") (pin "2") (pinfunction "2_2") (pintype "passive"))
      (node (ref "Q3") (pin "2") (pinfunction "S_2") (pintype "passive"))
    )
    (net (code "3") (name "5V_SAFE") (class "Default")
      (node (ref "JP1") (pin "3") (pinfunction "3_3") (pintype "passive"))
      (node (ref "Q4") (pin "2") (pinfunction "S_2") (pintype "passive"))
    )
    (net (code "4") (name "ADC") (class "Default")
      (node (ref "ESD16") (pin "C") (pinfunction "P$2_C") (pintype "bidirectional"))
      (node (ref "J1") (pin "12") (pinfunction "LRADC_12") (pintype "passive"))
      (node (ref "JP1") (pin "5") (pinfunction "5_5") (pintype "passive"))
    )
    (net (code "5") (name "COL-0") (class "Default")
      (node (ref "1") (pin "SW@1") (pinfunction "SW_SW@1") (pintype "bidirectional"))
      (node (ref "1") (pin "SW@2") (pinfunction "SW_SW@2") (pintype "bidirectional"))
      (node (ref "A") (pin "SW@1") (pinfunction "SW_SW@1") (pintype "bidirectional"))
      (node (ref "A") (pin "SW@2") (pinfunction "SW_SW@2") (pintype "bidirectional"))
      (node (ref "CTRL") (pin "SW@1") (pinfunction "SW_SW@1") (pintype "bidirectional"))
      (node (ref "CTRL") (pin "SW@2") (pinfunction "SW_SW@2") (pintype "bidirectional"))
      (node (ref "ESC") (pin "SW@1") (pinfunction "SW_SW@1") (pintype "bidirectional"))
      (node (ref "ESC") (pin "SW@2") (pinfunction "SW_SW@2") (pintype "bidirectional"))
      (node (ref "Q") (pin "SW@1") (pinfunction "SW_SW@1") (pintype "bidirectional"))
      (node (ref "Q") (pin "SW@2") (pinfunction "SW_SW@2") (pintype "bidirectional"))
      (node (ref "SHIFT") (pin "SW@1") (pinfunction "SW_SW@1") (pintype "bidirectional"))
      (node (ref "SHIFT") (pin "SW@2") (pinfunction "SW_SW@2") (pintype "bidirectional"))
      (node (ref "U2") (pin "9") (pinfunction "COL0_9") (pintype "bidirectional"))
    )
    (net (code "6") (name "COL-1") (class "Default")
      (node (ref "-") (pin "SW@1") (pinfunction "SW_SW@1") (pintype "bidirectional"))
      (node (ref "-") (pin "SW@2") (pinfunction "SW_SW@2") (pintype "bidirectional"))
      (node (ref "2") (pin "SW@1") (pinfunction "SW_SW@1") (pintype "bidirectional"))
      (node (ref "2") (pin "SW@2") (pinfunction "SW_SW@2") (pintype "bidirectional"))
      (node (ref "FN") (pin "SW") (pinfunction "SW_SW") (pintype "bidirectional"))
      (node (ref "FN") (pin "SW1") (pinfunction "SW_SW1") (pintype "bidirectional"))
      (node (ref "S") (pin "SW") (pinfunction "SW_SW") (pintype "bidirectional"))
      (node (ref "S") (pin "SW1") (pinfunction "SW_SW1") (pintype "bidirectional"))
      (node (ref "U2") (pin "10") (pinfunction "COL1_10") (pintype "bidirectional"))
      (node (ref "W") (pin "SW") (pinfunction "SW_SW") (pintype "bidirectional"))
      (node (ref "W") (pin "SW1") (pinfunction "SW_SW1") (pintype "bidirectional"))
      (node (ref "Z") (pin "SW") (pinfunction "SW_SW") (pintype "bidirectional"))
      (node (ref "Z") (pin "SW1") (pinfunction "SW_SW1") (pintype "bidirectional"))
    )
    (net (code "7") (name "COL-2") (class "Default")
      (node (ref "+") (pin "SW@1") (pinfunction "SW_SW@1") (pintype "bidirectional"))
      (node (ref "+") (pin "SW@2") (pinfunction "SW_SW@2") (pintype "bidirectional"))
      (node (ref "3") (pin "SW@1") (pinfunction "SW_SW@1") (pintype "bidirectional"))
      (node (ref "3") (pin "SW@2") (pinfunction "SW_SW@2") (pintype "bidirectional"))
      (node (ref "ALT") (pin "SW") (pinfunction "SW_SW") (pintype "bidirectional"))
      (node (ref "ALT") (pin "SW1") (pinfunction "SW_SW1") (pintype "bidirectional"))
      (node (ref "D") (pin "SW") (pinfunction "SW_SW") (pintype "bidirectional"))
      (node (ref "D") (pin "SW1") (pinfunction "SW_SW1") (pintype "bidirectional"))
      (node (ref "E") (pin "SW") (pinfunction "SW_SW") (pintype "bidirectional"))
      (node (ref "E") (pin "SW1") (pinfunction "SW_SW1") (pintype "bidirectional"))
      (node (ref "U2") (pin "11") (pinfunction "COL2_11") (pintype "bidirectional"))
      (node (ref "X") (pin "SW") (pinfunction "SW_SW") (pintype "bidirectional"))
      (node (ref "X") (pin "SW1") (pinfunction "SW_SW1") (pintype "bidirectional"))
    )
    (net (code "8") (name "COL-3") (class "Default")
      (node (ref "4") (pin "SW@1") (pinfunction "SW_SW@1") (pintype "bidirectional"))
      (node (ref "4") (pin "SW@2") (pinfunction "SW_SW@2") (pintype "bidirectional"))
      (node (ref "BKSPC") (pin "SW") (pinfunction "SW_SW") (pintype "bidirectional"))
      (node (ref "BKSPC") (pin "SW1") (pinfunction "SW_SW1") (pintype "bidirectional"))
      (node (ref "C") (pin "SW") (pinfunction "SW_SW") (pintype "bidirectional"))
      (node (ref "C") (pin "SW1") (pinfunction "SW_SW1") (pintype "bidirectional"))
      (node (ref "F") (pin "SW") (pinfunction "SW_SW") (pintype "bidirectional"))
      (node (ref "F") (pin "SW1") (pinfunction "SW_SW1") (pintype "bidirectional"))
      (node (ref "R") (pin "SW") (pinfunction "SW_SW") (pintype "bidirectional"))
      (node (ref "R") (pin "SW1") (pinfunction "SW_SW1") (pintype "bidirectional"))
      (node (ref "SPACEL") (pin "SW") (pinfunction "SW_SW") (pintype "bidirectional"))
      (node (ref "SPACEL") (pin "SW1") (pinfunction "SW_SW1") (pintype "bidirectional"))
      (node (ref "SPACER") (pin "SW") (pinfunction "SW_SW") (pintype "bidirectional"))
      (node (ref "SPACER") (pin "SW1") (pinfunction "SW_SW1") (pintype "bidirectional"))
      (node (ref "U2") (pin "12") (pinfunction "COL3_12") (pintype "bidirectional"))
    )
    (net (code "9") (name "COL-4") (class "Default")
      (node (ref "'") (pin "SW@1") (pinfunction "SW_SW@1") (pintype "bidirectional"))
      (node (ref "'") (pin "SW@2") (pinfunction "SW_SW@2") (pintype "bidirectional"))
      (node (ref "5") (pin "SW@1") (pinfunction "SW_SW@1") (pintype "bidirectional"))
      (node (ref "5") (pin "SW@2") (pinfunction "SW_SW@2") (pintype "bidirectional"))
      (node (ref "G") (pin "SW") (pinfunction "SW_SW") (pintype "bidirectional"))
      (node (ref "G") (pin "SW1") (pinfunction "SW_SW1") (pintype "bidirectional"))
      (node (ref "T") (pin "SW") (pinfunction "SW_SW") (pintype "bidirectional"))
      (node (ref "T") (pin "SW1") (pinfunction "SW_SW1") (pintype "bidirectional"))
      (node (ref "TAB") (pin "SW") (pinfunction "SW_SW") (pintype "bidirectional"))
      (node (ref "TAB") (pin "SW1") (pinfunction "SW_SW1") (pintype "bidirectional"))
      (node (ref "U2") (pin "13") (pinfunction "COL4_13") (pintype "bidirectional"))
      (node (ref "V") (pin "SW") (pinfunction "SW_SW") (pintype "bidirectional"))
      (node (ref "V") (pin "SW1") (pinfunction "SW_SW1") (pintype "bidirectional"))
    )
    (net (code "10") (name "COL-5") (class "Default")
      (node (ref "6") (pin "SW@1") (pinfunction "SW_SW@1") (pintype "bidirectional"))
      (node (ref "6") (pin "SW@2") (pinfunction "SW_SW@2") (pintype "bidirectional"))
      (node (ref "?/") (pin "SW") (pinfunction "SW_SW") (pintype "bidirectional"))
      (node (ref "?/") (pin "SW1") (pinfunction "SW_SW1") (pintype "bidirectional"))
      (node (ref "B") (pin "SW") (pinfunction "SW_SW") (pintype "bidirectional"))
      (node (ref "B") (pin "SW1") (pinfunction "SW_SW1") (pintype "bidirectional"))
      (node (ref "H") (pin "SW") (pinfunction "SW_SW") (pintype "bidirectional"))
      (node (ref "H") (pin "SW1") (pinfunction "SW_SW1") (pintype "bidirectional"))
      (node (ref "U2") (pin "14") (pinfunction "COL5_14") (pintype "bidirectional"))
      (node (ref "Y") (pin "SW") (pinfunction "SW_SW") (pintype "bidirectional"))
      (node (ref "Y") (pin "SW1") (pinfunction "SW_SW1") (pintype "bidirectional"))
    )
    (net (code "11") (name "COL-6") (class "Default")
      (node (ref "7") (pin "SW@1") (pinfunction "SW_SW@1") (pintype "bidirectional"))
      (node (ref "7") (pin "SW@2") (pinfunction "SW_SW@2") (pintype "bidirectional"))
      (node (ref "J") (pin "SW") (pinfunction "SW_SW") (pintype "bidirectional"))
      (node (ref "J") (pin "SW1") (pinfunction "SW_SW1") (pintype "bidirectional"))
      (node (ref "N") (pin "SW") (pinfunction "SW_SW") (pintype "bidirectional"))
      (node (ref "N") (pin "SW1") (pinfunction "SW_SW1") (pintype "bidirectional"))
      (node (ref "SHFT") (pin "SW@1") (pinfunction "SW_SW@1") (pintype "bidirectional"))
      (node (ref "SHFT") (pin "SW@2") (pinfunction "SW_SW@2") (pintype "bidirectional"))
      (node (ref "U") (pin "SW") (pinfunction "SW_SW") (pintype "bidirectional"))
      (node (ref "U") (pin "SW1") (pinfunction "SW_SW1") (pintype "bidirectional"))
      (node (ref "U2") (pin "15") (pinfunction "COL6_15") (pintype "bidirectional"))
    )
    (net (code "12") (name "COL-7") (class "Default")
      (node (ref "8") (pin "SW@1") (pinfunction "SW_SW@1") (pintype "bidirectional"))
      (node (ref "8") (pin "SW@2") (pinfunction "SW_SW@2") (pintype "bidirectional"))
      (node (ref "I") (pin "SW") (pinfunction "SW_SW") (pintype "bidirectional"))
      (node (ref "I") (pin "SW1") (pinfunction "SW_SW1") (pintype "bidirectional"))
      (node (ref "K") (pin "SW") (pinfunction "SW_SW") (pintype "bidirectional"))
      (node (ref "K") (pin "SW1") (pinfunction "SW_SW1") (pintype "bidirectional"))
      (node (ref "M") (pin "SW@1") (pinfunction "SW_SW@1") (pintype "bidirectional"))
      (node (ref "M") (pin "SW@2") (pinfunction "SW_SW@2") (pintype "bidirectional"))
      (node (ref "U2") (pin "16") (pinfunction "COL7_16") (pintype "bidirectional"))
    )
    (net (code "13") (name "COL-8") (class "Default")
      (node (ref "9") (pin "SW@1") (pinfunction "SW_SW@1") (pintype "bidirectional"))
      (node (ref "9") (pin "SW@2") (pinfunction "SW_SW@2") (pintype "bidirectional"))
      (node (ref "L") (pin "SW") (pinfunction "SW_SW") (pintype "bidirectional"))
      (node (ref "L") (pin "SW1") (pinfunction "SW_SW1") (pintype "bidirectional"))
      (node (ref "LEFT") (pin "SW") (pinfunction "SW_SW") (pintype "bidirectional"))
      (node (ref "LEFT") (pin "SW1") (pinfunction "SW_SW1") (pintype "bidirectional"))
      (node (ref "O") (pin "SW") (pinfunction "SW_SW") (pintype "bidirectional"))
      (node (ref "O") (pin "SW1") (pinfunction "SW_SW1") (pintype "bidirectional"))
      (node (ref "U2") (pin "17") (pinfunction "COL8_17") (pintype "bidirectional"))
      (node (ref "UP") (pin "SW") (pinfunction "SW_SW") (pintype "bidirectional"))
      (node (ref "UP") (pin "SW1") (pinfunction "SW_SW1") (pintype "bidirectional"))
    )
    (net (code "14") (name "COL-9") (class "Default")
      (node (ref "0") (pin "SW@1") (pinfunction "SW_SW@1") (pintype "bidirectional"))
      (node (ref "0") (pin "SW@2") (pinfunction "SW_SW@2") (pintype "bidirectional"))
      (node (ref "DWN") (pin "SW") (pinfunction "SW_SW") (pintype "bidirectional"))
      (node (ref "DWN") (pin "SW1") (pinfunction "SW_SW1") (pintype "bidirectional"))
      (node (ref "ENTER") (pin "SW") (pinfunction "SW_SW") (pintype "bidirectional"))
      (node (ref "ENTER") (pin "SW1") (pinfunction "SW_SW1") (pintype "bidirectional"))
      (node (ref "P") (pin "SW@1") (pinfunction "SW_SW@1") (pintype "bidirectional"))
      (node (ref "P") (pin "SW@2") (pinfunction "SW_SW@2") (pintype "bidirectional"))
      (node (ref "RIGHT") (pin "SW") (pinfunction "SW_SW") (pintype "bidirectional"))
      (node (ref "RIGHT") (pin "SW1") (pinfunction "SW_SW1") (pintype "bidirectional"))
      (node (ref "U2") (pin "18") (pinfunction "COL9_18") (pintype "bidirectional"))
    )
    (net (code "15") (name "DCLK") (class "Default")
      (node (ref "J1") (pin "76") (pinfunction "LCD-CLK_76") (pintype "passive"))
      (node (ref "X1") (pin "30") (pinfunction "1_30") (pintype "passive"))
    )
    (net (code "16") (name "EN") (class "Default")
      (node (ref "J1") (pin "70") (pinfunction "LCD-D18_70") (pintype "passive"))
      (node (ref "R1") (pin "1") (pinfunction "1_1") (pintype "passive"))
      (node (ref "U1") (pin "4") (pinfunction "EN_4") (pintype "bidirectional"))
      (node (ref "X1") (pin "31") (pinfunction "1_31") (pintype "passive"))
    )
    (net (code "17") (name "FB") (class "Default")
      (node (ref "C1") (pin "2") (pinfunction "2_2") (pintype "passive"))
      (node (ref "R2") (pin "2") (pinfunction "2_2") (pintype "passive"))
      (node (ref "R3") (pin "1") (pinfunction "1_1") (pintype "passive"))
      (node (ref "U1") (pin "3") (pinfunction "FB_3") (pintype "bidirectional"))
    )
    (net (code "18") (name "FEL") (class "Default")
      (node (ref "ESD1") (pin "C") (pinfunction "P$2_C") (pintype "bidirectional"))
      (node (ref "J1") (pin "8") (pinfunction "UBOOT_8") (pintype "passive"))
      (node (ref "JP1") (pin "21") (pinfunction "21_21") (pintype "passive"))
    )
    (net (code "19") (name "GND") (class "Default")
      (node (ref "C10") (pin "2") (pinfunction "2_2") (pintype "passive"))
      (node (ref "C11") (pin "1") (pinfunction "1_1") (pintype "passive"))
      (node (ref "C12") (pin "1") (pinfunction "1_1") (pintype "passive"))
      (node (ref "C17") (pin "2") (pinfunction "2_2") (pintype "passive"))
      (node (ref "C18") (pin "2") (pinfunction "2_2") (pintype "passive"))
      (node (ref "C19") (pin "2") (pinfunction "2_2") (pintype "passive"))
      (node (ref "C2") (pin "2") (pinfunction "2_2") (pintype "passive"))
      (node (ref "C3") (pin "2") (pinfunction "2_2") (pintype "passive"))
      (node (ref "C4") (pin "2") (pinfunction "2_2") (pintype "passive"))
      (node (ref "C5") (pin "2") (pinfunction "2_2") (pintype "passive"))
      (node (ref "C6") (pin "2") (pinfunction "2_2") (pintype "passive"))
      (node (ref "C7") (pin "2") (pinfunction "2_2") (pintype "passive"))
      (node (ref "C8") (pin "2") (pinfunction "2_2") (pintype "passive"))
      (node (ref "C9") (pin "2") (pinfunction "2_2") (pintype "passive"))
      (node (ref "ESD1") (pin "A") (pinfunction "P$1_A") (pintype "bidirectional"))
      (node (ref "ESD10") (pin "A") (pinfunction "P$1_A") (pintype "bidirectional"))
      (node (ref "ESD11") (pin "A") (pinfunction "P$1_A") (pintype "bidirectional"))
      (node (ref "ESD12") (pin "A") (pinfunction "P$1_A") (pintype "bidirectional"))
      (node (ref "ESD13") (pin "A") (pinfunction "P$1_A") (pintype "bidirectional"))
      (node (ref "ESD14") (pin "A") (pinfunction "P$1_A") (pintype "bidirectional"))
      (node (ref "ESD15") (pin "A") (pinfunction "P$1_A") (pintype "bidirectional"))
      (node (ref "ESD16") (pin "A") (pinfunction "P$1_A") (pintype "bidirectional"))
      (node (ref "ESD17") (pin "C") (pinfunction "P$2_C") (pintype "bidirectional"))
      (node (ref "ESD2") (pin "A") (pinfunction "P$1_A") (pintype "bidirectional"))
      (node (ref "ESD3") (pin "A") (pinfunction "P$1_A") (pintype "bidirectional"))
      (node (ref "ESD4") (pin "A") (pinfunction "P$1_A") (pintype "bidirectional"))
      (node (ref "ESD5") (pin "A") (pinfunction "P$1_A") (pintype "bidirectional"))
      (node (ref "ESD6") (pin "A") (pinfunction "P$1_A") (pintype "bidirectional"))
      (node (ref "ESD7") (pin "A") (pinfunction "P$1_A") (pintype "bidirectional"))
      (node (ref "ESD8") (pin "A") (pinfunction "P$1_A") (pintype "bidirectional"))
      (node (ref "ESD9") (pin "A") (pinfunction "P$1_A") (pintype "bidirectional"))
      (node (ref "J1") (pin "2") (pinfunction "_GND_2") (pintype "passive"))
      (node (ref "J1") (pin "21") (pinfunction "_GND_21") (pintype "passive"))
      (node (ref "J1") (pin "22") (pinfunction "_GND_22") (pintype "passive"))
      (node (ref "J1") (pin "39") (pinfunction "_GND_39") (pintype "passive"))
      (node (ref "J1") (pin "40") (pinfunction "_GND_40") (pintype "passive"))
      (node (ref "J1") (pin "42") (pinfunction "_GND_42") (pintype "power_in"))
      (node (ref "J1") (pin "43") (pinfunction "_GND_43") (pintype "passive"))
      (node (ref "J1") (pin "51") (pinfunction "_GND_51") (pintype "passive"))
      (node (ref "J1") (pin "80") (pinfunction "_GND_80") (pintype "power_in"))
      (node (ref "J3") (pin "2") (pinfunction "2_2") (pintype "bidirectional"))
      (node (ref "JP1") (pin "20") (pinfunction "20_20") (pintype "passive"))
      (node (ref "JP1") (pin "23") (pinfunction "23_23") (pintype "passive"))
      (node (ref "JP1") (pin "24") (pinfunction "24_24") (pintype "passive"))
      (node (ref "JP1") (pin "25") (pinfunction "25_25") (pintype "passive"))
      (node (ref "PWR") (pin "GND") (pinfunction "GND_GND") (pintype "bidirectional"))
      (node (ref "Q3") (pin "1") (pinfunction "G_1") (pintype "passive"))
      (node (ref "Q4") (pin "1") (pinfunction "G_1") (pintype "passive"))
      (node (ref "R1") (pin "2") (pinfunction "2_2") (pintype "passive"))
      (node (ref "R13") (pin "1") (pinfunction "1_1") (pintype "passive"))
      (node (ref "R3") (pin "2") (pinfunction "2_2") (pintype "passive"))
      (node (ref "R8") (pin "1") (pinfunction "1_1") (pintype "passive"))
      (node (ref "U1") (pin "2") (pinfunction "GND_2") (pintype "bidirectional"))
      (node (ref "U2") (pin "19") (pinfunction "GND_19") (pintype "power_in"))
      (node (ref "U2") (pin "25") (pinfunction "PAD_25") (pintype "power_in"))
      (node (ref "U2") (pin "H1") (pinfunction "PAD_H1") (pintype "power_in"))
      (node (ref "U2") (pin "H2") (pinfunction "PAD_H2") (pintype "power_in"))
      (node (ref "U2") (pin "H3") (pinfunction "PAD_H3") (pintype "power_in"))
      (node (ref "U2") (pin "H4") (pinfunction "PAD_H4") (pintype "power_in"))
      (node (ref "U3") (pin "1") (pinfunction "GND_1") (pintype "bidirectional"))
      (node (ref "U4") (pin "10") (pinfunction "GND_10") (pintype "bidirectional"))
      (node (ref "U4") (pin "12") (pinfunction "GND_12") (pintype "bidirectional"))
      (node (ref "U4") (pin "5") (pinfunction "GND_5") (pintype "bidirectional"))
      (node (ref "U5") (pin "2") (pinfunction "GND_2") (pintype "bidirectional"))
      (node (ref "U5") (pin "6") (pinfunction "GND_6") (pintype "bidirectional"))
      (node (ref "X1") (pin "1") (pinfunction "1_1") (pintype "passive"))
      (node (ref "X1") (pin "13") (pinfunction "1_13") (pintype "passive"))
      (node (ref "X1") (pin "14") (pinfunction "1_14") (pintype "passive"))
      (node (ref "X1") (pin "21") (pinfunction "1_21") (pintype "passive"))
      (node (ref "X1") (pin "22") (pinfunction "1_22") (pintype "passive"))
      (node (ref "X1") (pin "29") (pinfunction "1_29") (pintype "passive"))
      (node (ref "X1") (pin "3") (pinfunction "1_3") (pintype "passive"))
      (node (ref "X1") (pin "36") (pinfunction "1_36") (pintype "passive"))
      (node (ref "X1") (pin "5") (pinfunction "1_5") (pintype "passive"))
      (node (ref "X1") (pin "6") (pinfunction "1_6") (pintype "passive"))
    )
    (net (code "20") (name "GP1") (class "Default")
      (node (ref "ESD15") (pin "C") (pinfunction "P$2_C") (pintype "bidirectional"))
      (node (ref "J1") (pin "16") (pinfunction "XIO-P2_16") (pintype "passive"))
      (node (ref "JP1") (pin "6") (pinfunction "6_6") (pintype "passive"))
    )
    (net (code "21") (name "GP2") (class "Default")
      (node (ref "ESD14") (pin "C") (pinfunction "P$2_C") (pintype "bidirectional"))
      (node (ref "J1") (pin "15") (pinfunction "XIO-P3_15") (pintype "passive"))
      (node (ref "JP1") (pin "7") (pinfunction "7_7") (pintype "passive"))
    )
    (net (code "22") (name "GP3") (class "Default")
      (node (ref "ESD13") (pin "C") (pinfunction "P$2_C") (pintype "bidirectional"))
      (node (ref "J1") (pin "18") (pinfunction "XIO-P4_18") (pintype "passive"))
      (node (ref "JP1") (pin "8") (pinfunction "8_8") (pintype "passive"))
    )
    (net (code "23") (name "GP4") (class "Default")
      (node (ref "ESD12") (pin "C") (pinfunction "P$2_C") (pintype "bidirectional"))
      (node (ref "J1") (pin "17") (pinfunction "XIO-P5_17") (pintype "passive"))
      (node (ref "JP1") (pin "9") (pinfunction "9_9") (pintype "passive"))
    )
    (net (code "24") (name "GP5") (class "Default")
      (node (ref "ESD11") (pin "C") (pinfunction "P$2_C") (pintype "bidirectional"))
      (node (ref "J1") (pin "20") (pinfunction "XIO-P6_20") (pintype "passive"))
      (node (ref "JP1") (pin "10") (pinfunction "10_10") (pintype "passive"))
    )
    (net (code "25") (name "GP6") (class "Default")
      (node (ref "ESD10") (pin "C") (pinfunction "P$2_C") (pintype "bidirectional"))
      (node (ref "J1") (pin "19") (pinfunction "XIO-P7_19") (pintype "passive"))
      (node (ref "JP1") (pin "11") (pinfunction "11_11") (pintype "passive"))
    )
    (net (code "26") (name "HSYNC") (class "Default")
      (node (ref "J1") (pin "77") (pinfunction "LCDHSYNC_77") (pintype "passive"))
      (node (ref "X1") (pin "32") (pinfunction "1_32") (pintype "passive"))
    )
    (net (code "27") (name "I2C-SCL") (class "Default")
      (node (ref "ESD4") (pin "C") (pinfunction "P$2_C") (pintype "bidirectional"))
      (node (ref "J1") (pin "25") (pinfunction "TWI2-SCK_25") (pintype "passive"))
      (node (ref "JP1") (pin "17") (pinfunction "17_17") (pintype "passive"))
      (node (ref "R16") (pin "1") (pinfunction "1_1") (pintype "passive"))
      (node (ref "U4") (pin "4") (pinfunction "SCL_4") (pintype "bidirectional"))
    )
    (net (code "28") (name "I2C-SDA") (class "Default")
      (node (ref "ESD5") (pin "C") (pinfunction "P$2_C") (pintype "bidirectional"))
      (node (ref "J1") (pin "26") (pinfunction "TWI2-SDA_26") (pintype "passive"))
      (node (ref "JP1") (pin "16") (pinfunction "16_16") (pintype "passive"))
      (node (ref "R17") (pin "1") (pinfunction "1_1") (pintype "passive"))
      (node (ref "U4") (pin "6") (pinfunction "SDA_6") (pintype "bidirectional"))
    )
    (net (code "29") (name "KPD_I2C_SCL") (class "Default")
      (node (ref "J1") (pin "52") (pinfunction "TWI1-SCK_52") (pintype "passive"))
      (node (ref "R4") (pin "1") (pinfunction "1_1") (pintype "passive"))
      (node (ref "U2") (pin "23") (pinfunction "SCL_23") (pintype "bidirectional"))
      (node (ref "U5") (pin "11") (pinfunction "SCL_11") (pintype "bidirectional"))
    )
    (net (code "30") (name "KPD_I2C_SDA") (class "Default")
      (node (ref "J1") (pin "50") (pinfunction "TWI1-SDA_50") (pintype "passive"))
      (node (ref "R5") (pin "1") (pinfunction "1_1") (pintype "passive"))
      (node (ref "U2") (pin "22") (pinfunction "SDA_22") (pintype "bidirectional"))
      (node (ref "U5") (pin "9") (pinfunction "SDA_9") (pintype "bidirectional"))
    )
    (net (code "31") (name "KPD_INT") (class "Default")
      (node (ref "J1") (pin "24") (pinfunction "AP-EINT1_24") (pintype "passive"))
      (node (ref "R10") (pin "2") (pinfunction "2_2") (pintype "passive"))
      (node (ref "TP3") (pin "1") (pinfunction "1_1") (pintype "bidirectional"))
      (node (ref "U2") (pin "24") (pinfunction "INT_24") (pintype "bidirectional"))
    )
    (net (code "32") (name "KPD_RST") (class "Default")
      (node (ref "R6") (pin "1") (pinfunction "1_1") (pintype "passive"))
      (node (ref "TP4") (pin "1") (pinfunction "1_1") (pintype "bidirectional"))
      (node (ref "U2") (pin "20") (pinfunction "RESET_20") (pintype "bidirectional"))
    )
    (net (code "33") (name "LCD_D3") (class "Default")
      (node (ref "J1") (pin "59") (pinfunction "LCD-D3_59") (pintype "passive"))
      (node (ref "X1") (pin "24") (pinfunction "1_24") (pintype "passive"))
    )
    (net (code "34") (name "LCD_D4") (class "Default")
      (node (ref "J1") (pin "60") (pinfunction "LCD-D4_60") (pintype "passive"))
      (node (ref "X1") (pin "25") (pinfunction "1_25") (pintype "passive"))
    )
    (net (code "35") (name "LCD_D5") (class "Default")
      (node (ref "J1") (pin "61") (pinfunction "LCD-D5_61") (pintype "passive"))
      (node (ref "X1") (pin "26") (pinfunction "1_26") (pintype "passive"))
    )
    (net (code "36") (name "LCD_D6") (class "Default")
      (node (ref "J1") (pin "62") (pinfunction "LCD-D6_62") (pintype "passive"))
      (node (ref "X1") (pin "27") (pinfunction "1_27") (pintype "passive"))
    )
    (net (code "37") (name "LCD_D7") (class "Default")
      (node (ref "J1") (pin "63") (pinfunction "LCD-D7_63") (pintype "passive"))
      (node (ref "X1") (pin "28") (pinfunction "1_28") (pintype "passive"))
    )
    (net (code "38") (name "LCD_D10") (class "Default")
      (node (ref "J1") (pin "64") (pinfunction "LCD-D10_64") (pintype "passive"))
      (node (ref "X1") (pin "15") (pinfunction "1_15") (pintype "passive"))
    )
    (net (code "39") (name "LCD_D11") (class "Default")
      (node (ref "J1") (pin "65") (pinfunction "LCD-D11_65") (pintype "passive"))
      (node (ref "X1") (pin "16") (pinfunction "1_16") (pintype "passive"))
    )
    (net (code "40") (name "LCD_D12") (class "Default")
      (node (ref "J1") (pin "66") (pinfunction "LCD-D12_66") (pintype "passive"))
      (node (ref "X1") (pin "17") (pinfunction "1_17") (pintype "passive"))
    )
    (net (code "41") (name "LCD_D13") (class "Default")
      (node (ref "J1") (pin "67") (pinfunction "LCD-D13_67") (pintype "passive"))
      (node (ref "X1") (pin "18") (pinfunction "1_18") (pintype "passive"))
    )
    (net (code "42") (name "LCD_D14") (class "Default")
      (node (ref "J1") (pin "68") (pinfunction "LCD-D14_68") (pintype "passive"))
      (node (ref "X1") (pin "19") (pinfunction "1_19") (pintype "passive"))
    )
    (net (code "43") (name "LCD_D15") (class "Default")
      (node (ref "J1") (pin "69") (pinfunction "LCD-D15_69") (pintype "passive"))
      (node (ref "X1") (pin "20") (pinfunction "1_20") (pintype "passive"))
    )
    (net (code "44") (name "LCD_D19") (class "Default")
      (node (ref "J1") (pin "71") (pinfunction "LCD-D19_71") (pintype "passive"))
      (node (ref "X1") (pin "8") (pinfunction "1_8") (pintype "passive"))
    )
    (net (code "45") (name "LCD_D20") (class "Default")
      (node (ref "J1") (pin "72") (pinfunction "LCD-D20_72") (pintype "passive"))
      (node (ref "X1") (pin "9") (pinfunction "1_9") (pintype "passive"))
    )
    (net (code "46") (name "LCD_D21") (class "Default")
      (node (ref "J1") (pin "73") (pinfunction "LCD-D21_73") (pintype "passive"))
      (node (ref "X1") (pin "10") (pinfunction "1_10") (pintype "passive"))
    )
    (net (code "47") (name "LCD_D22") (class "Default")
      (node (ref "J1") (pin "74") (pinfunction "LCD-D22_74") (pintype "passive"))
      (node (ref "X1") (pin "11") (pinfunction "1_11") (pintype "passive"))
    )
    (net (code "48") (name "LCD_D23") (class "Default")
      (node (ref "J1") (pin "75") (pinfunction "LCD-D23_75") (pintype "passive"))
      (node (ref "X1") (pin "12") (pinfunction "1_12") (pintype "passive"))
    )
    (net (code "49") (name "LCD_DE") (class "Default")
      (node (ref "J1") (pin "79") (pinfunction "LCD-DE_79") (pintype "passive"))
      (node (ref "X1") (pin "34") (pinfunction "1_34") (pintype "passive"))
    )
    (net (code "50") (name "LCD_XL") (class "Default")
      (node (ref "J1") (pin "54") (pinfunction "X1_54") (pintype "passive"))
      (node (ref "X1") (pin "39") (pinfunction "1_39") (pintype "passive"))
    )
    (net (code "51") (name "LCD_XR") (class "Default")
      (node (ref "J1") (pin "53") (pinfunction "X2_53") (pintype "passive"))
      (node (ref "X1") (pin "37") (pinfunction "1_37") (pintype "passive"))
    )
    (net (code "52") (name "LCD_YD") (class "Default")
      (node (ref "J1") (pin "55") (pinfunction "Y2_55") (pintype "passive"))
      (node (ref "X1") (pin "38") (pinfunction "1_38") (pintype "passive"))
    )
    (net (code "53") (name "LCD_YU") (class "Default")
      (node (ref "J1") (pin "56") (pinfunction "Y1_56") (pintype "passive"))
      (node (ref "X1") (pin "40") (pinfunction "1_40") (pintype "passive"))
    )
    (net (code "54") (name "N$61") (class "Default")
      (node (ref "Q2") (pin "3") (pinfunction "OUT_3") (pintype "passive"))
      (node (ref "X1") (pin "2") (pinfunction "1_2") (pintype "passive"))
    )
    (net (code "55") (name "Net-(L1-1)") (class "Default")
      (node (ref "D1") (pin "A") (pinfunction "A_A") (pintype "bidirectional"))
      (node (ref "L1") (pin "P$1") (pinfunction "1_P$1") (pintype "passive"))
      (node (ref "U1") (pin "1") (pinfunction "SW_1") (pintype "bidirectional"))
    )
    (net (code "56") (name "Net-(Q1-OUT)") (class "Default")
      (node (ref "Q1") (pin "3") (pinfunction "OUT_3") (pintype "passive"))
      (node (ref "Q2") (pin "1") (pinfunction "IN_1") (pintype "passive"))
    )
    (net (code "57") (name "Net-(U4-BYP)") (class "Default")
      (node (ref "C17") (pin "1") (pinfunction "1_1") (pintype "passive"))
      (node (ref "U4") (pin "2") (pinfunction "BYP_2") (pintype "bidirectional"))
    )
    (net (code "58") (name "Net-(U5-IREF)") (class "Default")
      (node (ref "R8") (pin "2") (pinfunction "2_2") (pintype "passive"))
      (node (ref "U5") (pin "10") (pinfunction "IREF_10") (pintype "bidirectional"))
    )
    (net (code "59") (name "Net-(U5-LED1)") (class "Default")
      (node (ref "LED1") (pin "RED") (pinfunction "RED_RED") (pintype "bidirectional"))
      (node (ref "U5") (pin "5") (pinfunction "LED1_5") (pintype "bidirectional"))
    )
    (net (code "60") (name "Net-(U5-LED2)") (class "Default")
      (node (ref "LED1") (pin "GREEN") (pinfunction "GREEN_GREEN") (pintype "bidirectional"))
      (node (ref "U5") (pin "4") (pinfunction "LED2_4") (pintype "bidirectional"))
    )
    (net (code "61") (name "Net-(U5-LED3)") (class "Default")
      (node (ref "LED1") (pin "BLUE") (pinfunction "BLUE_BLUE") (pintype "bidirectional"))
      (node (ref "U5") (pin "3") (pinfunction "LED3_3") (pintype "bidirectional"))
    )
    (net (code "62") (name "PWM") (class "Default")
      (node (ref "J1") (pin "57") (pinfunction "PWM0_57") (pintype "passive"))
      (node (ref "Q1") (pin "2") (pinfunction "GND_2") (pintype "passive"))
      (node (ref "R13") (pin "2") (pinfunction "2_2") (pintype "passive"))
    )
    (net (code "63") (name "PWR_LGT") (class "Default")
      (node (ref "C1") (pin "1") (pinfunction "1_1") (pintype "passive"))
      (node (ref "C3") (pin "1") (pinfunction "1_1") (pintype "passive"))
      (node (ref "C5") (pin "1") (pinfunction "1_1") (pintype "passive"))
      (node (ref "D1") (pin "C") (pinfunction "C_C") (pintype "bidirectional"))
      (node (ref "Q2") (pin "2") (pinfunction "GND_2") (pintype "passive"))
      (node (ref "R2") (pin "1") (pinfunction "1_1") (pintype "passive"))
      (node (ref "TP2") (pin "1") (pinfunction "1_1") (pintype "bidirectional"))
    )
    (net (code "64") (name "PWR_ON") (class "Default")
      (node (ref "J1") (pin "49") (pinfunction "PWRON_49") (pintype "passive"))
      (node (ref "PWR") (pin "SW") (pinfunction "SW_SW") (pintype "bidirectional"))
      (node (ref "PWR") (pin "SW1") (pinfunction "SW_SW1") (pintype "bidirectional"))
      (node (ref "R9") (pin "1") (pinfunction "1_1") (pintype "passive"))
    )
    (net (code "65") (name "ROW-0") (class "Default")
      (node (ref "0") (pin "GND") (pinfunction "GND_GND") (pintype "bidirectional"))
      (node (ref "1") (pin "GND") (pinfunction "GND_GND") (pintype "bidirectional"))
      (node (ref "2") (pin "GND") (pinfunction "GND_GND") (pintype "bidirectional"))
      (node (ref "3") (pin "GND") (pinfunction "GND_GND") (pintype "bidirectional"))
      (node (ref "4") (pin "GND") (pinfunction "GND_GND") (pintype "bidirectional"))
      (node (ref "5") (pin "GND") (pinfunction "GND_GND") (pintype "bidirectional"))
      (node (ref "6") (pin "GND") (pinfunction "GND_GND") (pintype "bidirectional"))
      (node (ref "7") (pin "GND") (pinfunction "GND_GND") (pintype "bidirectional"))
      (node (ref "8") (pin "GND") (pinfunction "GND_GND") (pintype "bidirectional"))
      (node (ref "9") (pin "GND") (pinfunction "GND_GND") (pintype "bidirectional"))
      (node (ref "U2") (pin "8") (pinfunction "ROW0_8") (pintype "bidirectional"))
    )
    (net (code "66") (name "ROW-1") (class "Default")
      (node (ref "E") (pin "GND") (pinfunction "GND_GND") (pintype "bidirectional"))
      (node (ref "E") (pin "GND@1") (pinfunction "GND_GND@1") (pintype "bidirectional"))
      (node (ref "I") (pin "GND") (pinfunction "GND_GND") (pintype "bidirectional"))
      (node (ref "I") (pin "GND@1") (pinfunction "GND_GND@1") (pintype "bidirectional"))
      (node (ref "O") (pin "GND") (pinfunction "GND_GND") (pintype "bidirectional"))
      (node (ref "O") (pin "GND@1") (pinfunction "GND_GND@1") (pintype "bidirectional"))
      (node (ref "P") (pin "GND") (pinfunction "GND_GND") (pintype "bidirectional"))
      (node (ref "Q") (pin "GND") (pinfunction "GND_GND") (pintype "bidirectional"))
      (node (ref "R") (pin "GND") (pinfunction "GND_GND") (pintype "bidirectional"))
      (node (ref "R") (pin "GND@1") (pinfunction "GND_GND@1") (pintype "bidirectional"))
      (node (ref "T") (pin "GND") (pinfunction "GND_GND") (pintype "bidirectional"))
      (node (ref "T") (pin "GND@1") (pinfunction "GND_GND@1") (pintype "bidirectional"))
      (node (ref "U") (pin "GND") (pinfunction "GND_GND") (pintype "bidirectional"))
      (node (ref "U") (pin "GND@1") (pinfunction "GND_GND@1") (pintype "bidirectional"))
      (node (ref "U2") (pin "7") (pinfunction "ROW1_7") (pintype "bidirectional"))
      (node (ref "W") (pin "GND") (pinfunction "GND_GND") (pintype "bidirectional"))
      (node (ref "W") (pin "GND@1") (pinfunction "GND_GND@1") (pintype "bidirectional"))
      (node (ref "Y") (pin "GND") (pinfunction "GND_GND") (pintype "bidirectional"))
      (node (ref "Y") (pin "GND@1") (pinfunction "GND_GND@1") (pintype "bidirectional"))
    )
    (net (code "67") (name "ROW-2") (class "Default")
      (node (ref "A") (pin "GND") (pinfunction "GND_GND") (pintype "bidirectional"))
      (node (ref "D") (pin "GND") (pinfunction "GND_GND") (pintype "bidirectional"))
      (node (ref "D") (pin "GND@1") (pinfunction "GND_GND@1") (pintype "bidirectional"))
      (node (ref "ENTER") (pin "GND") (pinfunction "GND_GND") (pintype "bidirectional"))
      (node (ref "F") (pin "GND") (pinfunction "GND_GND") (pintype "bidirectional"))
      (node (ref "F") (pin "GND@1") (pinfunction "GND_GND@1") (pintype "bidirectional"))
      (node (ref "G") (pin "GND") (pinfunction "GND_GND") (pintype "bidirectional"))
      (node (ref "G") (pin "GND@1") (pinfunction "GND_GND@1") (pintype "bidirectional"))
      (node (ref "H") (pin "GND") (pinfunction "GND_GND") (pintype "bidirectional"))
      (node (ref "H") (pin "GND@1") (pinfunction "GND_GND@1") (pintype "bidirectional"))
      (node (ref "J") (pin "GND") (pinfunction "GND_GND") (pintype "bidirectional"))
      (node (ref "J") (pin "GND@1") (pinfunction "GND_GND@1") (pintype "bidirectional"))
      (node (ref "K") (pin "GND") (pinfunction "GND_GND") (pintype "bidirectional"))
      (node (ref "K") (pin "GND@1") (pinfunction "GND_GND@1") (pintype "bidirectional"))
      (node (ref "L") (pin "GND") (pinfunction "GND_GND") (pintype "bidirectional"))
      (node (ref "L") (pin "GND@1") (pinfunction "GND_GND@1") (pintype "bidirectional"))
      (node (ref "S") (pin "GND") (pinfunction "GND_GND") (pintype "bidirectional"))
      (node (ref "S") (pin "GND@1") (pinfunction "GND_GND@1") (pintype "bidirectional"))
      (node (ref "U2") (pin "6") (pinfunction "ROW2_6") (pintype "bidirectional"))
    )
    (net (code "68") (name "ROW-3") (class "Default")
      (node (ref "B") (pin "GND") (pinfunction "GND_GND") (pintype "bidirectional"))
      (node (ref "B") (pin "GND@1") (pinfunction "GND_GND@1") (pintype "bidirectional"))
      (node (ref "C") (pin "GND") (pinfunction "GND_GND") (pintype "bidirectional"))
      (node (ref "C") (pin "GND@1") (pinfunction "GND_GND@1") (pintype "bidirectional"))
      (node (ref "DWN") (pin "GND") (pinfunction "GND_GND") (pintype "bidirectional"))
      (node (ref "M") (pin "GND") (pinfunction "GND_GND") (pintype "bidirectional"))
      (node (ref "N") (pin "GND") (pinfunction "GND_GND") (pintype "bidirectional"))
      (node (ref "N") (pin "GND@1") (pinfunction "GND_GND@1") (pintype "bidirectional"))
      (node (ref "SHIFT") (pin "GND") (pinfunction "GND_GND") (pintype "bidirectional"))
      (node (ref "U2") (pin "5") (pinfunction "ROW3_5") (pintype "bidirectional"))
      (node (ref "UP") (pin "GND") (pinfunction "GND_GND") (pintype "bidirectional"))
      (node (ref "V") (pin "GND") (pinfunction "GND_GND") (pintype "bidirectional"))
      (node (ref "V") (pin "GND@1") (pinfunction "GND_GND@1") (pintype "bidirectional"))
      (node (ref "X") (pin "GND") (pinfunction "GND_GND") (pintype "bidirectional"))
      (node (ref "X") (pin "GND@1") (pinfunction "GND_GND@1") (pintype "bidirectional"))
      (node (ref "Z") (pin "GND") (pinfunction "GND_GND") (pintype "bidirectional"))
      (node (ref "Z") (pin "GND@1") (pinfunction "GND_GND@1") (pintype "bidirectional"))
    )
    (net (code "69") (name "ROW-4") (class "Default")
      (node (ref "?/") (pin "GND") (pinfunction "GND_GND") (pintype "bidirectional"))
      (node (ref "?/") (pin "GND@1") (pinfunction "GND_GND@1") (pintype "bidirectional"))
      (node (ref "ALT") (pin "GND") (pinfunction "GND_GND") (pintype "bidirectional"))
      (node (ref "ALT") (pin "GND@1") (pinfunction "GND_GND@1") (pintype "bidirectional"))
      (node (ref "ESC") (pin "GND") (pinfunction "GND_GND") (pintype "bidirectional"))
      (node (ref "FN") (pin "GND") (pinfunction "GND_GND") (pintype "bidirectional"))
      (node (ref "FN") (pin "GND@1") (pinfunction "GND_GND@1") (pintype "bidirectional"))
      (node (ref "LEFT") (pin "GND") (pinfunction "GND_GND") (pintype "bidirectional"))
      (node (ref "RIGHT") (pin "GND") (pinfunction "GND_GND") (pintype "bidirectional"))
      (node (ref "SHFT") (pin "GND") (pinfunction "GND_GND") (pintype "bidirectional"))
      (node (ref "SPACEL") (pin "GND") (pinfunction "GND_GND") (pintype "bidirectional"))
      (node (ref "SPACEL") (pin "GND@1") (pinfunction "GND_GND@1") (pintype "bidirectional"))
      (node (ref "SPACER") (pin "GND") (pinfunction "GND_GND") (pintype "bidirectional"))
      (node (ref "SPACER") (pin "GND@1") (pinfunction "GND_GND@1") (pintype "bidirectional"))
      (node (ref "TAB") (pin "GND") (pinfunction "GND_GND") (pintype "bidirectional"))
      (node (ref "TAB") (pin "GND@1") (pinfunction "GND_GND@1") (pintype "bidirectional"))
      (node (ref "U2") (pin "4") (pinfunction "ROW4_4") (pintype "bidirectional"))
    )
    (net (code "70") (name "ROW-5") (class "Default")
      (node (ref "'") (pin "GND") (pinfunction "GND_GND") (pintype "bidirectional"))
      (node (ref "+") (pin "GND") (pinfunction "GND_GND") (pintype "bidirectional"))
      (node (ref "-") (pin "GND") (pinfunction "GND_GND") (pintype "bidirectional"))
      (node (ref "BKSPC") (pin "GND") (pinfunction "GND_GND") (pintype "bidirectional"))
      (node (ref "CTRL") (pin "GND") (pinfunction "GND_GND") (pintype "bidirectional"))
      (node (ref "U2") (pin "3") (pinfunction "ROW5_3") (pintype "bidirectional"))
    )
    (net (code "71") (name "ROW-6") (class "Default")
      (node (ref "R11") (pin "1") (pinfunction "1_1") (pintype "passive"))
      (node (ref "U2") (pin "2") (pinfunction "ROW6_2") (pintype "bidirectional"))
    )
    (net (code "72") (name "ROW-7") (class "Default")
      (node (ref "R7") (pin "1") (pinfunction "1_1") (pintype "passive"))
      (node (ref "U2") (pin "1") (pinfunction "ROW7_1") (pintype "bidirectional"))
    )
    (net (code "73") (name "SA0") (class "Default")
      (node (ref "R18") (pin "1") (pinfunction "1_1") (pintype "passive"))
      (node (ref "U4") (pin "7") (pinfunction "SA0_7") (pintype "bidirectional"))
    )
    (net (code "74") (name "SPI-CLK") (class "Default")
      (node (ref "ESD9") (pin "C") (pinfunction "P$2_C") (pintype "bidirectional"))
      (node (ref "J1") (pin "27") (pinfunction "CSICK_27") (pintype "passive"))
      (node (ref "JP1") (pin "12") (pinfunction "12_12") (pintype "passive"))
    )
    (net (code "75") (name "SPI-MISO") (class "Default")
      (node (ref "ESD7") (pin "C") (pinfunction "P$2_C") (pintype "bidirectional"))
      (node (ref "J1") (pin "29") (pinfunction "CSIVSYNC_29") (pintype "passive"))
      (node (ref "JP1") (pin "14") (pinfunction "14_14") (pintype "passive"))
    )
    (net (code "76") (name "SPI-MOSI") (class "Default")
      (node (ref "ESD8") (pin "C") (pinfunction "P$2_C") (pintype "bidirectional"))
      (node (ref "J1") (pin "30") (pinfunction "CSIHSYNC_30") (pintype "passive"))
      (node (ref "JP1") (pin "13") (pinfunction "13_13") (pintype "passive"))
    )
    (net (code "77") (name "SPI-SEL") (class "Default")
      (node (ref "ESD6") (pin "C") (pinfunction "P$2_C") (pintype "bidirectional"))
      (node (ref "J1") (pin "28") (pinfunction "CSIPCK_28") (pintype "passive"))
      (node (ref "JP1") (pin "15") (pinfunction "15_15") (pintype "passive"))
    )
    (net (code "78") (name "UART_RX") (class "Default")
      (node (ref "ESD3") (pin "C") (pinfunction "P$2_C") (pintype "bidirectional"))
      (node (ref "J1") (pin "6") (pinfunction "UART1-RX_6") (pintype "passive"))
      (node (ref "JP1") (pin "18") (pinfunction "18_18") (pintype "passive"))
    )
    (net (code "79") (name "UART_TX") (class "Default")
      (node (ref "ESD2") (pin "C") (pinfunction "P$2_C") (pintype "bidirectional"))
      (node (ref "J1") (pin "4") (pinfunction "UART1-TX_4") (pintype "passive"))
      (node (ref "JP1") (pin "19") (pinfunction "19_19") (pintype "passive"))
    )
    (net (code "80") (name "VBAT_EXT") (class "Default")
      (node (ref "C2") (pin "1") (pinfunction "1_1") (pintype "passive"))
      (node (ref "C4") (pin "1") (pinfunction "1_1") (pintype "passive"))
      (node (ref "ESD17") (pin "A") (pinfunction "P$1_A") (pintype "bidirectional"))
      (node (ref "J1") (pin "47") (pinfunction "VBAT-EXT_47") (pintype "passive"))
      (node (ref "J3") (pin "1") (pinfunction "1_1") (pintype "bidirectional"))
      (node (ref "JP1") (pin "4") (pinfunction "4_4") (pintype "passive"))
      (node (ref "L1") (pin "P$2") (pinfunction "2_P$2") (pintype "passive"))
      (node (ref "TP1") (pin "1") (pinfunction "1_1") (pintype "bidirectional"))
      (node (ref "U1") (pin "5") (pinfunction "VIN_5") (pintype "bidirectional"))
    )
    (net (code "81") (name "VCC3V3") (class "Default")
      (node (ref "C11") (pin "2") (pinfunction "2_2") (pintype "passive"))
      (node (ref "C12") (pin "2") (pinfunction "2_2") (pintype "passive"))
      (node (ref "C18") (pin "1") (pinfunction "1_1") (pintype "passive"))
      (node (ref "C19") (pin "1") (pinfunction "1_1") (pintype "passive"))
      (node (ref "C6") (pin "1") (pinfunction "1_1") (pintype "passive"))
      (node (ref "C9") (pin "1") (pinfunction "1_1") (pintype "passive"))
      (node (ref "J1") (pin "10") (pinfunction "VCC3V3_10") (pintype "passive"))
      (node (ref "J1") (pin "46") (pinfunction "VCC3V3_46") (pintype "bidirectional"))
      (node (ref "LED1") (pin "VIN") (pinfunction "VIN_VIN") (pintype "bidirectional"))
      (node (ref "Q1") (pin "1") (pinfunction "IN_1") (pintype "passive"))
      (node (ref "Q3") (pin "3") (pinfunction "D_3") (pintype "passive"))
      (node (ref "R10") (pin "1") (pinfunction "1_1") (pintype "passive"))
      (node (ref "R11") (pin "2") (pinfunction "2_2") (pintype "passive"))
      (node (ref "R12") (pin "2") (pinfunction "2_2") (pintype "passive"))
      (node (ref "R16") (pin "2") (pinfunction "2_2") (pintype "passive"))
      (node (ref "R17") (pin "2") (pinfunction "2_2") (pintype "passive"))
      (node (ref "R18") (pin "2") (pinfunction "2_2") (pintype "passive"))
      (node (ref "R4") (pin "2") (pinfunction "2_2") (pintype "passive"))
      (node (ref "R5") (pin "2") (pinfunction "2_2") (pintype "passive"))
      (node (ref "R6") (pin "2") (pinfunction "2_2") (pintype "passive"))
      (node (ref "R7") (pin "2") (pinfunction "2_2") (pintype "passive"))
      (node (ref "R9") (pin "2") (pinfunction "2_2") (pintype "passive"))
      (node (ref "U2") (pin "21") (pinfunction "VCC_21") (pintype "power_in"))
      (node (ref "U4") (pin "1") (pinfunction "VDDIO_1") (pintype "bidirectional"))
      (node (ref "U4") (pin "14") (pinfunction "VDD_14") (pintype "bidirectional"))
      (node (ref "U5") (pin "12") (pinfunction "VDET_12") (pintype "bidirectional"))
      (node (ref "U5") (pin "13") (pinfunction "VBAT_13") (pintype "bidirectional"))
      (node (ref "X1") (pin "4") (pinfunction "1_4") (pintype "passive"))
    )
    (net (code "82") (name "VCC5V") (class "Default")
      (node (ref "C10") (pin "1") (pinfunction "1_1") (pintype "passive"))
      (node (ref "C7") (pin "1") (pinfunction "1_1") (pintype "passive"))
      (node (ref "C8") (pin "1") (pinfunction "1_1") (pintype "passive"))
      (node (ref "J1") (pin "1") (pinfunction "VCC-5V_1") (pintype "passive"))
      (node (ref "J1") (pin "44") (pinfunction "VCC-5V_44") (pintype "bidirectional"))
      (node (ref "Q4") (pin "3") (pinfunction "D_3") (pintype "passive"))
    )
    (net (code "83") (name "VSYNC") (class "Default")
      (node (ref "J1") (pin "78") (pinfunction "LCDVSYNC_78") (pintype "passive"))
      (node (ref "X1") (pin "33") (pinfunction "1_33") (pintype "passive"))
    )
    (net (code "84") (name "unconnected-(J1-ACIN-5V-Pad41)") (class "Default")
      (node (ref "J1") (pin "41") (pinfunction "ACIN-5V_41") (pintype "passive"))
    )
    (net (code "85") (name "unconnected-(J1-AP-EINT3-Pad23)") (class "Default")
      (node (ref "J1") (pin "23") (pinfunction "AP-EINT3_23") (pintype "passive"))
    )
    (net (code "86") (name "unconnected-(J1-CSID0-Pad32)") (class "Default")
      (node (ref "J1") (pin "32") (pinfunction "CSID0_32") (pintype "passive"))
    )
    (net (code "87") (name "unconnected-(J1-CSID1-Pad31)") (class "Default")
      (node (ref "J1") (pin "31") (pinfunction "CSID1_31") (pintype "passive"))
    )
    (net (code "88") (name "unconnected-(J1-CSID2-Pad34)") (class "Default")
      (node (ref "J1") (pin "34") (pinfunction "CSID2_34") (pintype "passive"))
    )
    (net (code "89") (name "unconnected-(J1-CSID3-Pad33)") (class "Default")
      (node (ref "J1") (pin "33") (pinfunction "CSID3_33") (pintype "passive"))
    )
    (net (code "90") (name "unconnected-(J1-CSID4-Pad36)") (class "Default")
      (node (ref "J1") (pin "36") (pinfunction "CSID4_36") (pintype "passive"))
    )
    (net (code "91") (name "unconnected-(J1-CSID5-Pad35)") (class "Default")
      (node (ref "J1") (pin "35") (pinfunction "CSID5_35") (pintype "passive"))
    )
    (net (code "92") (name "unconnected-(J1-CSID6-Pad38)") (class "Default")
      (node (ref "J1") (pin "38") (pinfunction "CSID6_38") (pintype "passive"))
    )
    (net (code "93") (name "unconnected-(J1-CSID7-Pad37)") (class "Default")
      (node (ref "J1") (pin "37") (pinfunction "CSID7_37") (pintype "passive"))
    )
    (net (code "94") (name "unconnected-(J1-HPCOM-Pad5)") (class "Default")
      (node (ref "J1") (pin "5") (pinfunction "HPCOM_5") (pintype "passive"))
    )
    (net (code "95") (name "unconnected-(J1-HPL-Pad3)") (class "Default")
      (node (ref "J1") (pin "3") (pinfunction "HPL_3") (pintype "passive"))
    )
    (net (code "96") (name "unconnected-(J1-HPR-Pad7)") (class "Default")
      (node (ref "J1") (pin "7") (pinfunction "HPR_7") (pintype "passive"))
    )
    (net (code "97") (name "unconnected-(J1-MICIN1-Pad11)") (class "Default")
      (node (ref "J1") (pin "11") (pinfunction "MICIN1_11") (pintype "passive"))
    )
    (net (code "98") (name "unconnected-(J1-MICM-Pad9)") (class "Default")
      (node (ref "J1") (pin "9") (pinfunction "MICM_9") (pintype "passive"))
    )
    (net (code "99") (name "unconnected-(J1-TS-Pad45)") (class "Default")
      (node (ref "J1") (pin "45") (pinfunction "TS_45") (pintype "passive"))
    )
    (net (code "100") (name "unconnected-(J1-VCC-1V8-Pad48)") (class "Default")
      (node (ref "J1") (pin "48") (pinfunction "VCC-1V8_48") (pintype "bidirectional"))
    )
    (net (code "101") (name "unconnected-(J1-XIO-P0-Pad14)") (class "Default")
      (node (ref "J1") (pin "14") (pinfunction "XIO-P0_14") (pintype "passive"))
    )
    (net (code "102") (name "unconnected-(J1-XIO-P1-Pad13)") (class "Default")
      (node (ref "J1") (pin "13") (pinfunction "XIO-P1_13") (pintype "passive"))
    )
    (net (code "103") (name "unconnected-(J3-PadMNT1)") (class "Default")
      (node (ref "J3") (pin "MNT1") (pinfunction "MNT1_MNT1") (pintype "no_connect"))
    )
    (net (code "104") (name "unconnected-(J3-PadMNT2)") (class "Default")
      (node (ref "J3") (pin "MNT2") (pinfunction "MNT2_MNT2") (pintype "no_connect"))
    )
    (net (code "105") (name "unconnected-(JP1-Pad1)") (class "Default")
      (node (ref "JP1") (pin "1") (pinfunction "1_1") (pintype "passive"))
    )
    (net (code "106") (name "unconnected-(JP1-Pad22)") (class "Default")
      (node (ref "JP1") (pin "22") (pinfunction "22_22") (pintype "passive"))
    )
    (net (code "107") (name "unconnected-(U3-NC-Pad3)") (class "Default")
      (node (ref "U3") (pin "3") (pinfunction "NC_3") (pintype "bidirectional"))
    )
    (net (code "108") (name "unconnected-(U3-NC-Pad4)") (class "Default")
      (node (ref "U3") (pin "4") (pinfunction "NC_4") (pintype "bidirectional"))
    )
    (net (code "109") (name "unconnected-(U3-NC-Pad5)") (class "Default")
      (node (ref "U3") (pin "5") (pinfunction "NC_5") (pintype "bidirectional"))
    )
    (net (code "110") (name "unconnected-(U3-NC-Pad6)") (class "Default")
      (node (ref "U3") (pin "6") (pinfunction "NC_6") (pintype "bidirectional"))
    )
    (net (code "111") (name "unconnected-(U4-INT1-Pad11)") (class "Default")
      (node (ref "U4") (pin "11") (pinfunction "INT1_11") (pintype "bidirectional"))
    )
    (net (code "112") (name "unconnected-(U4-INT2-Pad9)") (class "Default")
      (node (ref "U4") (pin "9") (pinfunction "INT2_9") (pintype "bidirectional"))
    )
    (net (code "113") (name "unconnected-(U5-IC-Pad1)") (class "Default")
      (node (ref "U5") (pin "1") (pinfunction "IC_1") (pintype "bidirectional"))
    )
    (net (code "114") (name "unconnected-(U5-NC-Pad7)") (class "Default")
      (node (ref "U5") (pin "7") (pinfunction "NC_7") (pintype "bidirectional"))
    )
    (net (code "115") (name "unconnected-(U5-NC-Pad8)") (class "Default")
      (node (ref "U5") (pin "8") (pinfunction "NC_8") (pintype "bidirectional"))
    )
    (net (code "116") (name "unconnected-(U5-NC-Pad14)") (class "Default")
      (node (ref "U5") (pin "14") (pinfunction "NC_14") (pintype "bidirectional"))
    )
    (net (code "117") (name "unconnected-(X1AC-1-Pad35)") (class "Default")
      (node (ref "X1") (pin "35") (pinfunction "1_35") (pintype "passive"))
    )
    (net (code "118") (name "unconnected-(X1AL-1-Pad7)") (class "Default")
      (node (ref "X1") (pin "7") (pinfunction "1_7") (pintype "passive"))
    )
    (net (code "119") (name "unconnected-(X1P-1-Pad23)") (class "Default")
      (node (ref "X1") (pin "23") (pinfunction "1_23") (pintype "passive"))
    )
  )
)
